# NN22_VCCS_SrcAdapter02_s00.net
KiCad netlist of a schematic drawn in EAGLE
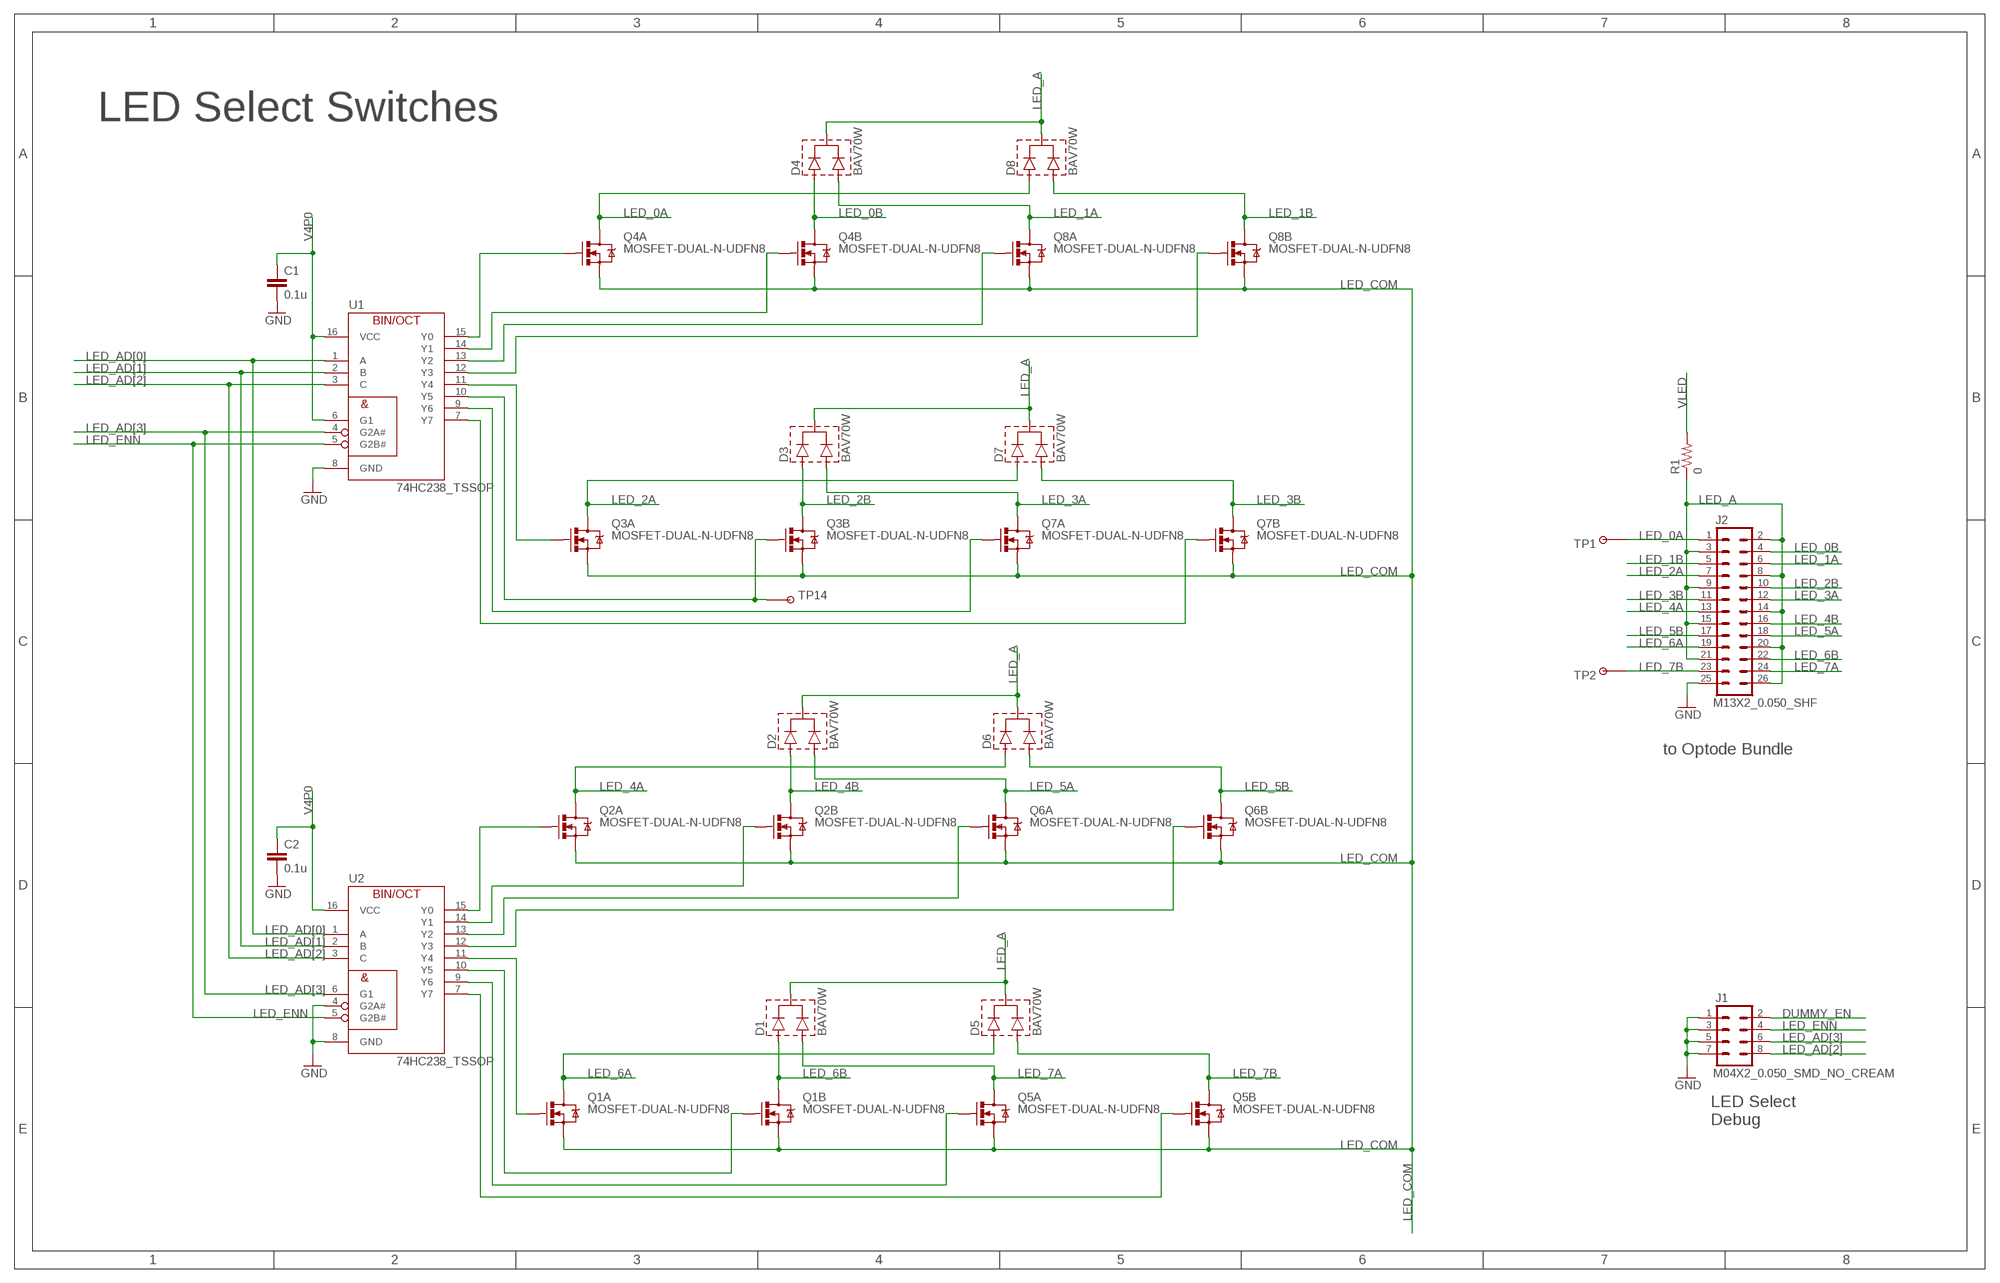
[diagram p0: schematic, sheet 1]
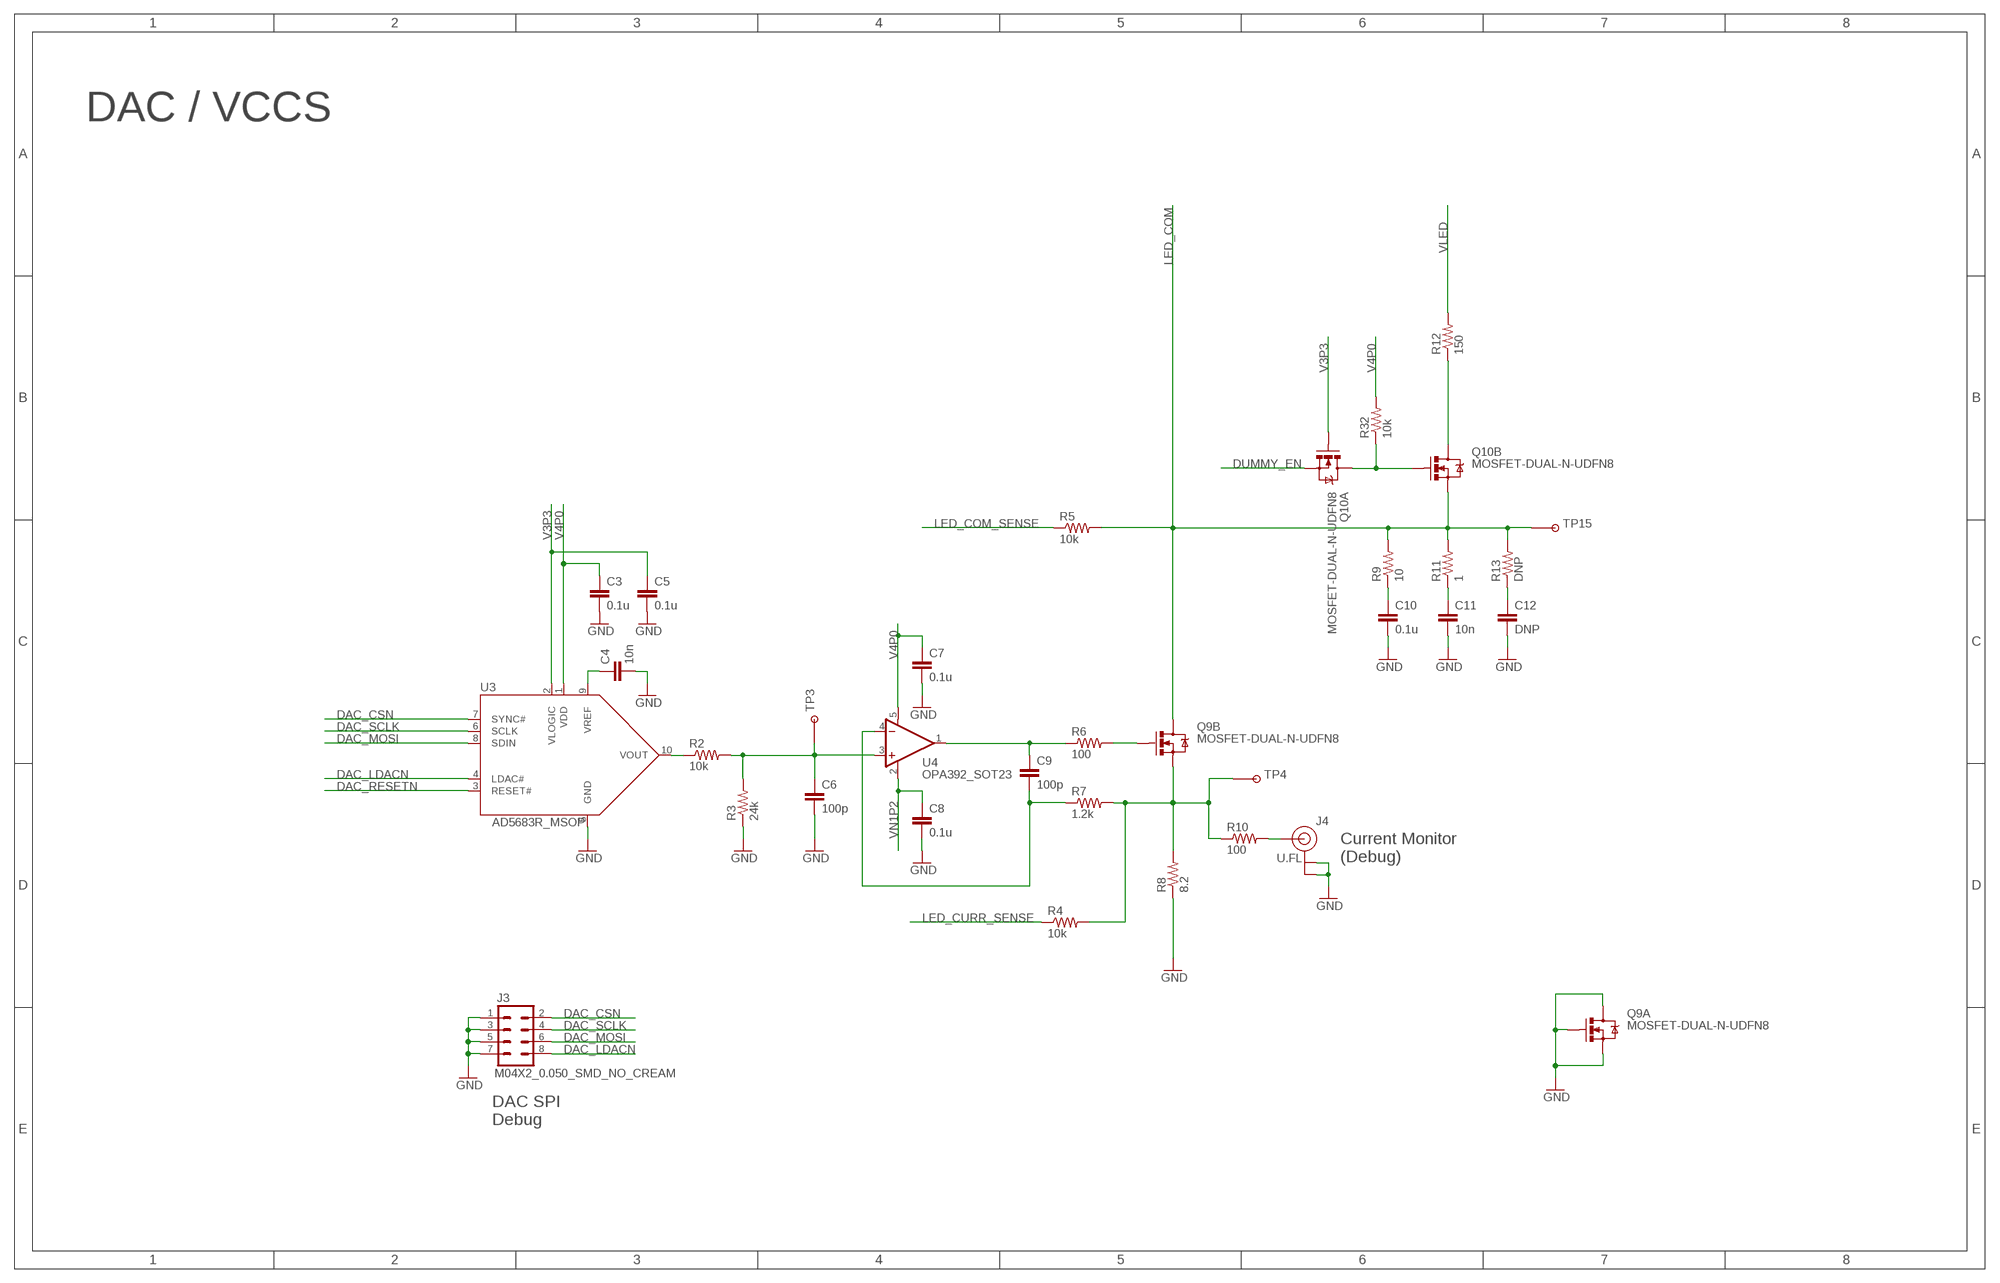
[diagram p1: schematic, sheet 2]
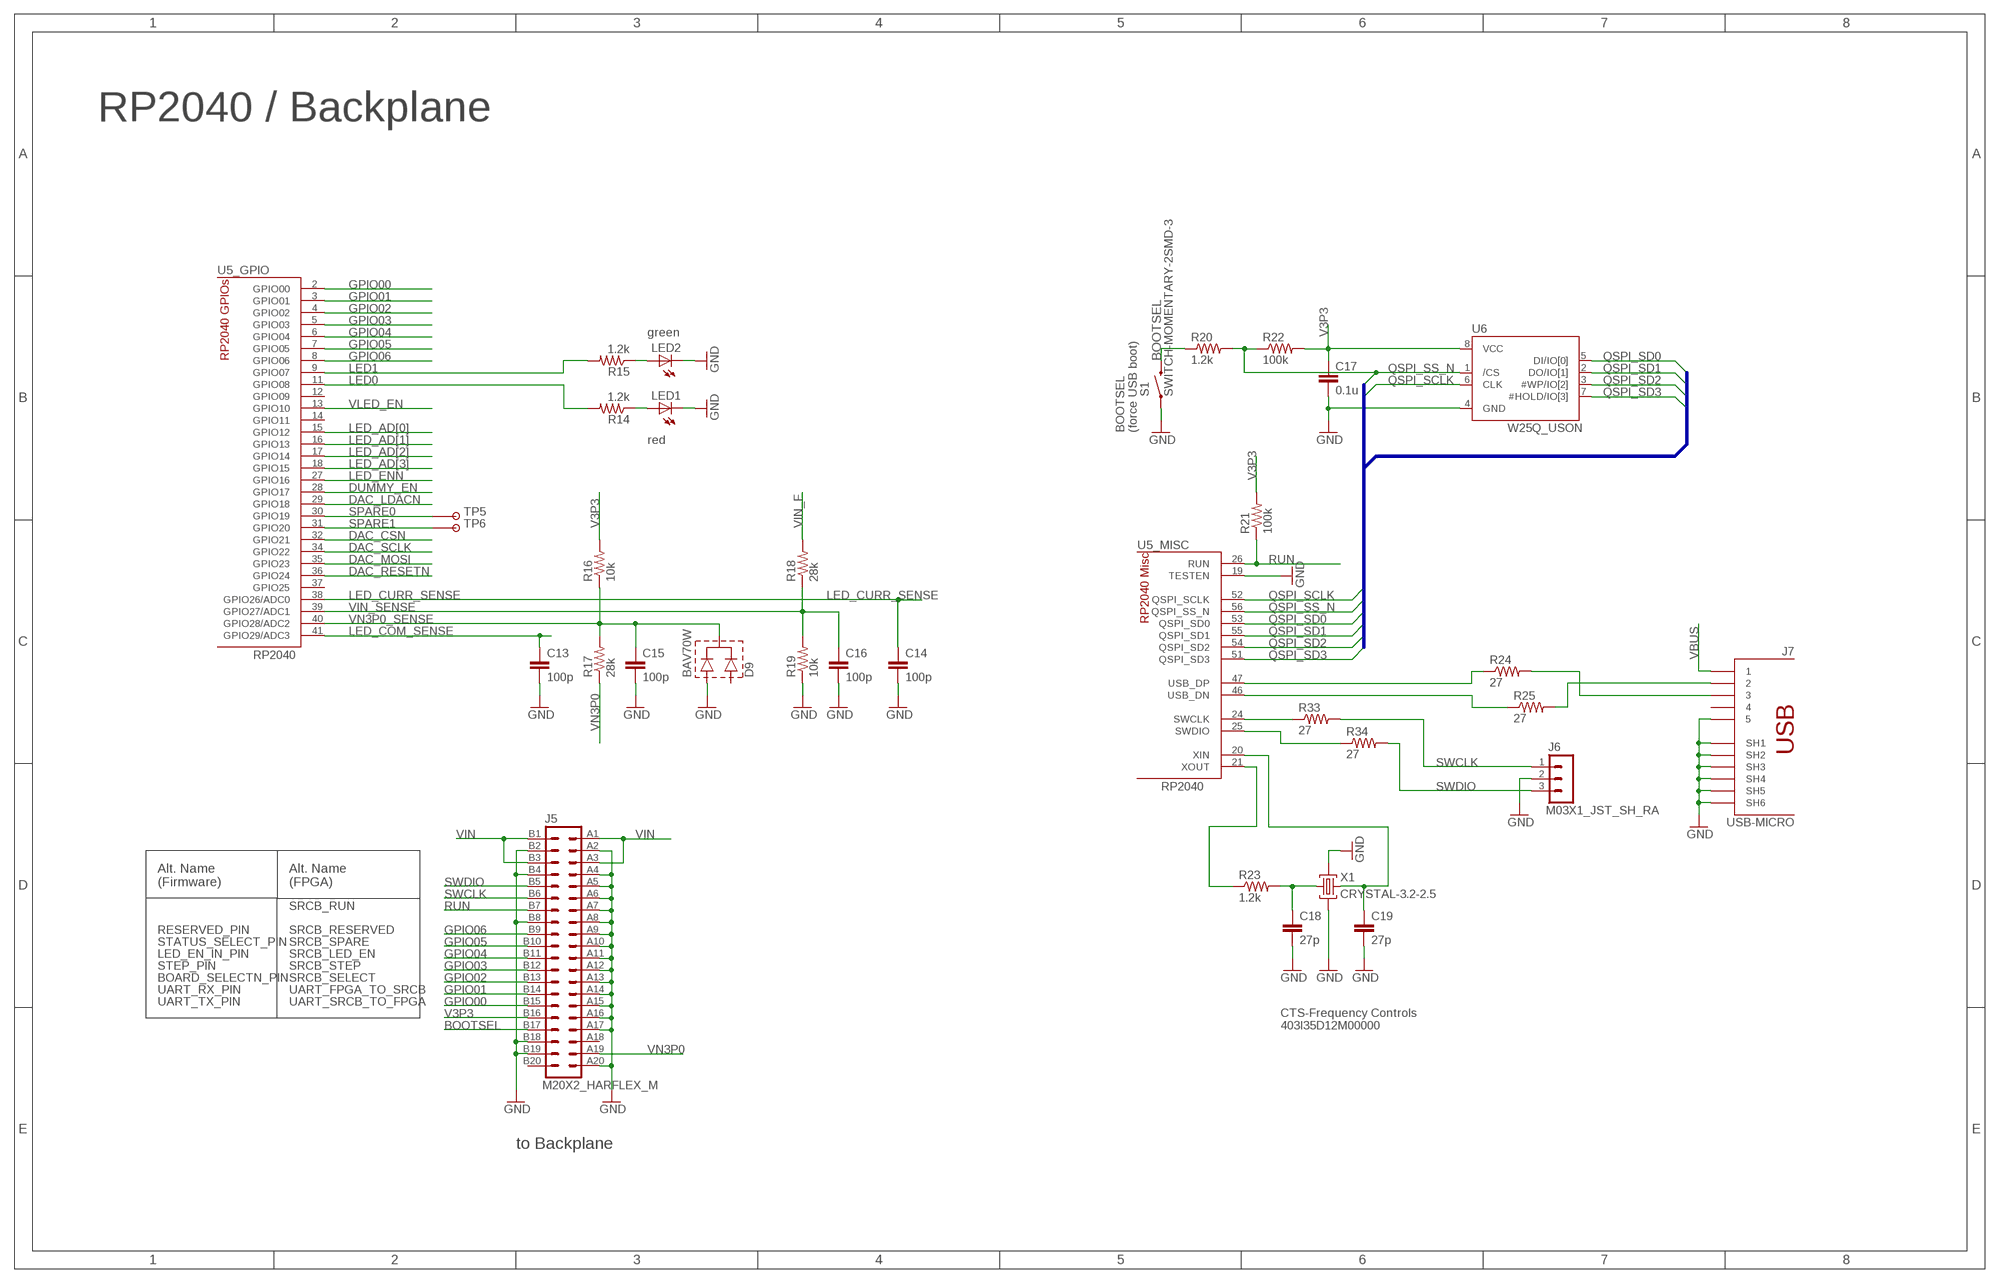
[diagram p2: schematic, sheet 3]
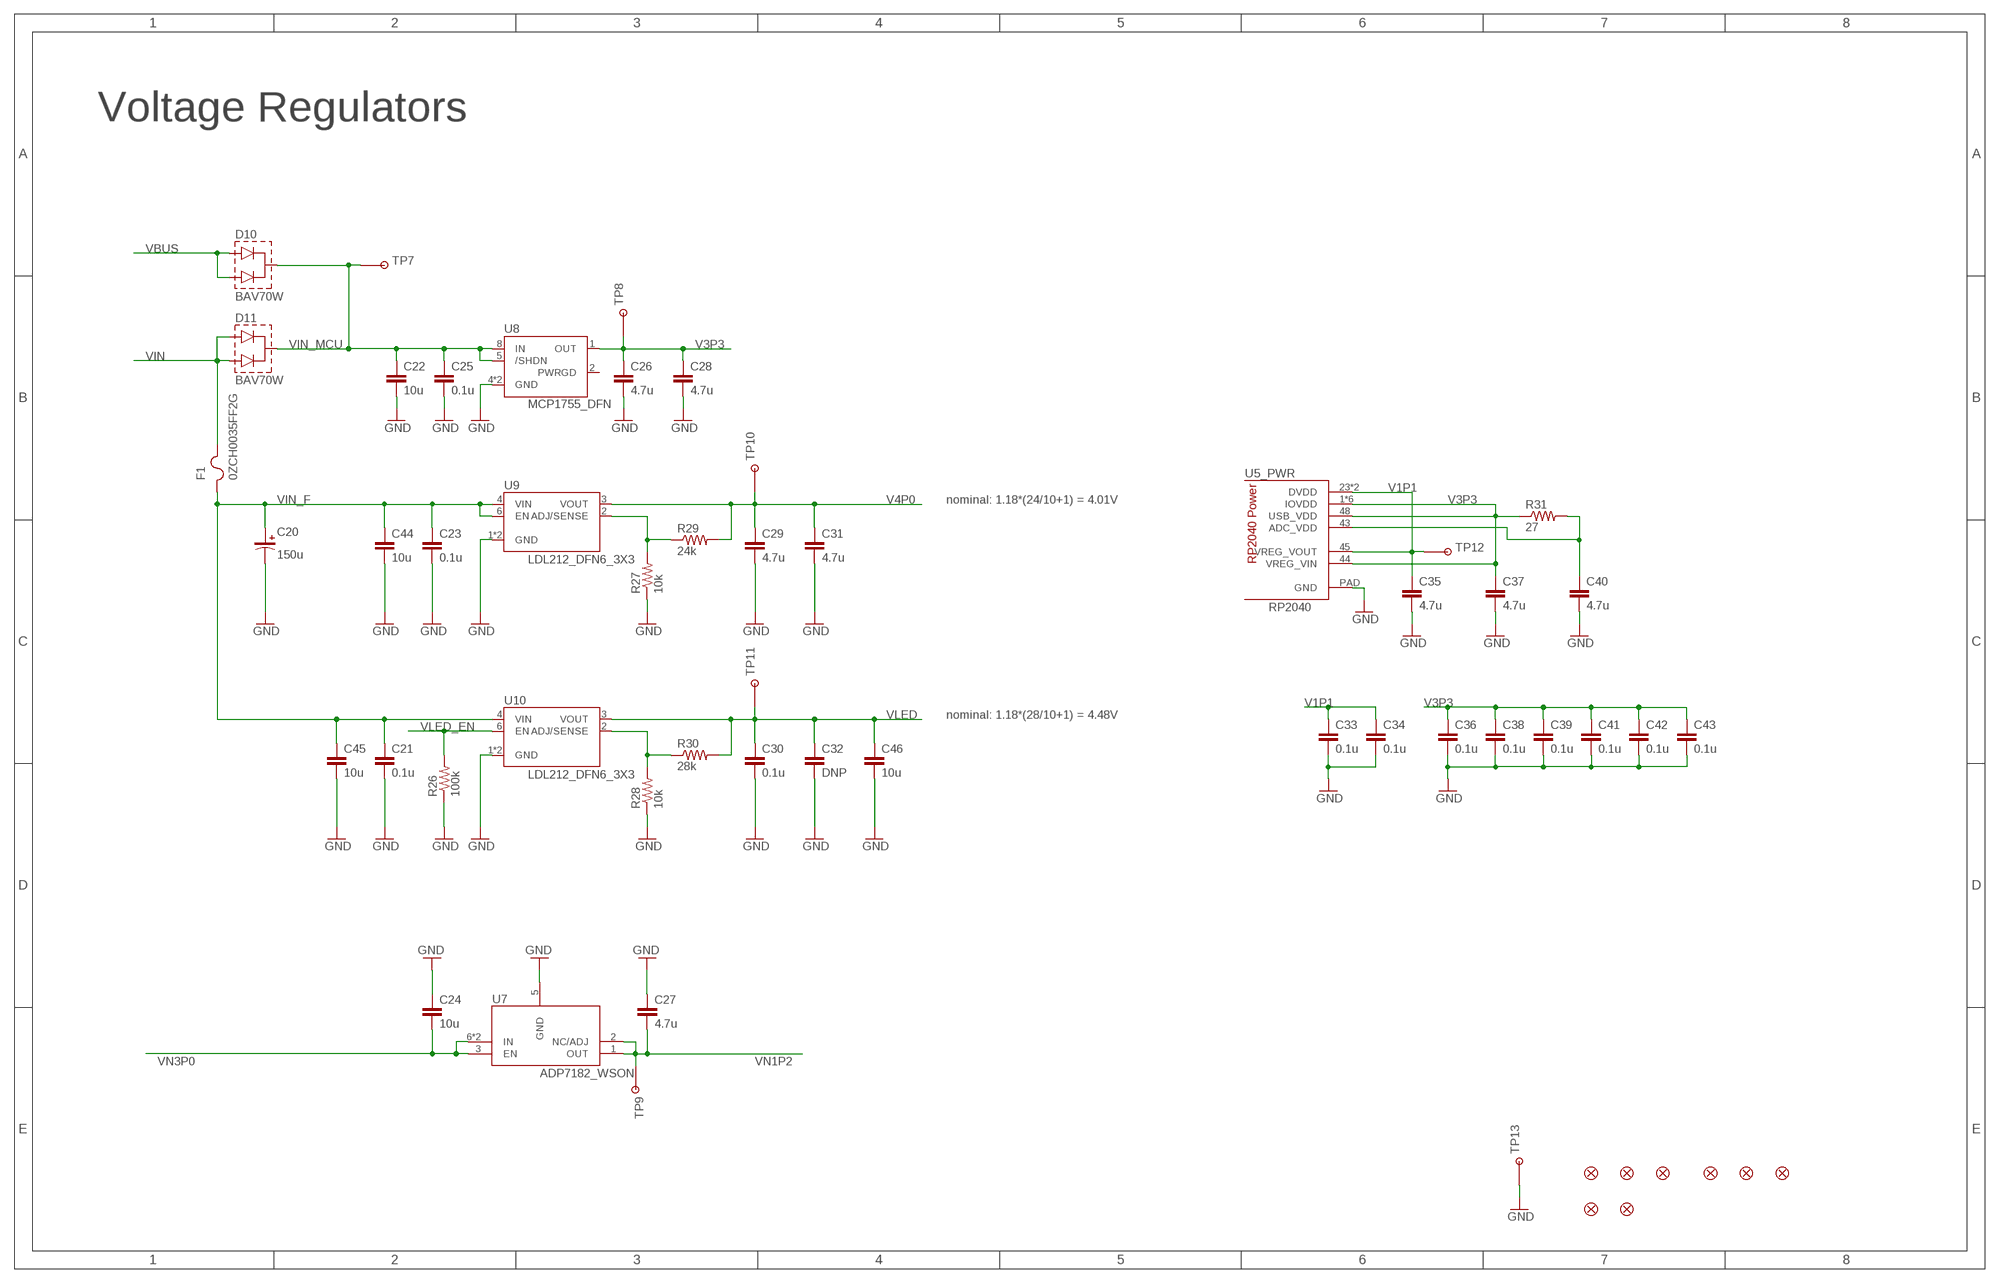
[diagram p3: schematic, sheet 4]

(export (version "E")
  (design (tool "Eeschema 10.0.6"))
  (components
    (comp (ref "C20")
      (value "150u")
      (footprint "eagle-import:2917-CAP")
      (libsource (lib "eagle-import") (part "CAP-POL2917"))
    )
    (comp (ref "C21")
      (value "0.1u")
      (footprint "eagle-import:0402-CAP")
      (libsource (lib "eagle-import") (part "CAP0402-CAP"))
    )
    (comp (ref "C22")
      (value "10u")
      (footprint "eagle-import:0603-CAP")
      (libsource (lib "eagle-import") (part "CAP0603-CAP"))
    )
    (comp (ref "C23")
      (value "0.1u")
      (footprint "eagle-import:0402-CAP")
      (libsource (lib "eagle-import") (part "CAP0402-CAP"))
    )
    (comp (ref "C24")
      (value "10u")
      (footprint "eagle-import:0603-CAP")
      (libsource (lib "eagle-import") (part "CAP0603-CAP"))
    )
    (comp (ref "C25")
      (value "0.1u")
      (footprint "eagle-import:0402-CAP")
      (libsource (lib "eagle-import") (part "CAP0402-CAP"))
    )
    (comp (ref "C26")
      (value "4.7u")
      (footprint "eagle-import:0402-CAP")
      (libsource (lib "eagle-import") (part "CAP0402-CAP"))
    )
    (comp (ref "C27")
      (value "4.7u")
      (footprint "eagle-import:0402-CAP")
      (libsource (lib "eagle-import") (part "CAP0402-CAP"))
    )
    (comp (ref "C28")
      (value "4.7u")
      (footprint "eagle-import:0402-CAP")
      (libsource (lib "eagle-import") (part "CAP0402-CAP"))
    )
    (comp (ref "C29")
      (value "4.7u")
      (footprint "eagle-import:0402-CAP")
      (libsource (lib "eagle-import") (part "CAP0402-CAP"))
    )
    (comp (ref "C30")
      (value "0.1u")
      (footprint "eagle-import:0402-CAP")
      (libsource (lib "eagle-import") (part "CAP0402-CAP"))
    )
    (comp (ref "C31")
      (value "4.7u")
      (footprint "eagle-import:0402-CAP")
      (libsource (lib "eagle-import") (part "CAP0402-CAP"))
    )
    (comp (ref "C32")
      (value "DNP")
      (footprint "eagle-import:0402-CAP")
      (libsource (lib "eagle-import") (part "CAP0402-CAP"))
    )
    (comp (ref "C33")
      (value "0.1u")
      (footprint "eagle-import:0402-CAP")
      (libsource (lib "eagle-import") (part "CAP0402-CAP"))
    )
    (comp (ref "C34")
      (value "0.1u")
      (footprint "eagle-import:0402-CAP")
      (libsource (lib "eagle-import") (part "CAP0402-CAP"))
    )
    (comp (ref "C35")
      (value "4.7u")
      (footprint "eagle-import:0402-CAP")
      (libsource (lib "eagle-import") (part "CAP0402-CAP"))
    )
    (comp (ref "C36")
      (value "0.1u")
      (footprint "eagle-import:0402-CAP")
      (libsource (lib "eagle-import") (part "CAP0402-CAP"))
    )
    (comp (ref "C37")
      (value "4.7u")
      (footprint "eagle-import:0402-CAP")
      (libsource (lib "eagle-import") (part "CAP0402-CAP"))
    )
    (comp (ref "C38")
      (value "0.1u")
      (footprint "eagle-import:0402-CAP")
      (libsource (lib "eagle-import") (part "CAP0402-CAP"))
    )
    (comp (ref "C39")
      (value "0.1u")
      (footprint "eagle-import:0402-CAP")
      (libsource (lib "eagle-import") (part "CAP0402-CAP"))
    )
    (comp (ref "C40")
      (value "4.7u")
      (footprint "eagle-import:0402-CAP")
      (libsource (lib "eagle-import") (part "CAP0402-CAP"))
    )
    (comp (ref "C41")
      (value "0.1u")
      (footprint "eagle-import:0402-CAP")
      (libsource (lib "eagle-import") (part "CAP0402-CAP"))
    )
    (comp (ref "C42")
      (value "0.1u")
      (footprint "eagle-import:0402-CAP")
      (libsource (lib "eagle-import") (part "CAP0402-CAP"))
    )
    (comp (ref "C43")
      (value "0.1u")
      (footprint "eagle-import:0402-CAP")
      (libsource (lib "eagle-import") (part "CAP0402-CAP"))
    )
    (comp (ref "C44")
      (value "10u")
      (footprint "eagle-import:0603-CAP")
      (libsource (lib "eagle-import") (part "CAP0603-CAP"))
    )
    (comp (ref "C45")
      (value "10u")
      (footprint "eagle-import:0603-CAP")
      (libsource (lib "eagle-import") (part "CAP0603-CAP"))
    )
    (comp (ref "C46")
      (value "10u")
      (footprint "eagle-import:0603-CAP")
      (libsource (lib "eagle-import") (part "CAP0603-CAP"))
    )
    (comp (ref "D10")
      (value "BAV70W")
      (footprint "eagle-import:SOT323")
      (libsource (lib "eagle-import") (part "DIODE-COMMON_CATHODE_SOT323"))
    )
    (comp (ref "D11")
      (value "BAV70W")
      (footprint "eagle-import:SOT323")
      (libsource (lib "eagle-import") (part "DIODE-COMMON_CATHODE_SOT323"))
    )
    (comp (ref "F1")
      (value "0ZCH0035FF2G")
      (footprint "eagle-import:1210-FUSE")
      (libsource (lib "eagle-import") (part "FUSE_1210"))
    )
    (comp (ref "FID1")
      (value "FIDUCIALUFIDUCIAL")
      (footprint "eagle-import:MICRO-FIDUCIAL")
      (libsource (lib "eagle-import") (part "FIDUCIALUFIDUCIAL"))
    )
    (comp (ref "FID2")
      (value "FIDUCIALUFIDUCIAL")
      (footprint "eagle-import:MICRO-FIDUCIAL")
      (libsource (lib "eagle-import") (part "FIDUCIALUFIDUCIAL"))
    )
    (comp (ref "FID3")
      (value "FIDUCIALUFIDUCIAL")
      (footprint "eagle-import:MICRO-FIDUCIAL")
      (libsource (lib "eagle-import") (part "FIDUCIALUFIDUCIAL"))
    )
    (comp (ref "FID4")
      (value "FIDUCIALUFIDUCIAL")
      (footprint "eagle-import:MICRO-FIDUCIAL")
      (libsource (lib "eagle-import") (part "FIDUCIALUFIDUCIAL"))
    )
    (comp (ref "FID5")
      (value "FIDUCIALUFIDUCIAL")
      (footprint "eagle-import:MICRO-FIDUCIAL")
      (libsource (lib "eagle-import") (part "FIDUCIALUFIDUCIAL"))
    )
    (comp (ref "FID6")
      (value "FIDUCIALUFIDUCIAL")
      (footprint "eagle-import:MICRO-FIDUCIAL")
      (libsource (lib "eagle-import") (part "FIDUCIALUFIDUCIAL"))
    )
    (comp (ref "FID7")
      (value "FIDUCIALUFIDUCIAL")
      (footprint "eagle-import:MICRO-FIDUCIAL")
      (libsource (lib "eagle-import") (part "FIDUCIALUFIDUCIAL"))
    )
    (comp (ref "FID8")
      (value "FIDUCIALUFIDUCIAL")
      (footprint "eagle-import:MICRO-FIDUCIAL")
      (libsource (lib "eagle-import") (part "FIDUCIALUFIDUCIAL"))
    )
    (comp (ref "R26")
      (value "100k")
      (footprint "eagle-import:0402-RES")
      (libsource (lib "eagle-import") (part "RESISTOR0402-RES"))
    )
    (comp (ref "R27")
      (value "10k")
      (footprint "eagle-import:0402-RES")
      (libsource (lib "eagle-import") (part "RESISTOR0402-RES"))
    )
    (comp (ref "R28")
      (value "10k")
      (footprint "eagle-import:0402-RES")
      (libsource (lib "eagle-import") (part "RESISTOR0402-RES"))
    )
    (comp (ref "R29")
      (value "24k")
      (footprint "eagle-import:0402-RES")
      (libsource (lib "eagle-import") (part "RESISTOR0402-RES"))
    )
    (comp (ref "R30")
      (value "28k")
      (footprint "eagle-import:0402-RES")
      (libsource (lib "eagle-import") (part "RESISTOR0402-RES"))
    )
    (comp (ref "R31")
      (value "27")
      (footprint "eagle-import:0402-RES")
      (libsource (lib "eagle-import") (part "RESISTOR0402-RES"))
    )
    (comp (ref "TP7")
      (value "TESTPOINT_ROUND")
      (footprint "eagle-import:TESTPAD_ROUND")
      (libsource (lib "eagle-import") (part "TESTPOINT_ROUND"))
    )
    (comp (ref "TP8")
      (value "TESTPOINT_ROUND")
      (footprint "eagle-import:TESTPAD_ROUND")
      (libsource (lib "eagle-import") (part "TESTPOINT_ROUND"))
    )
    (comp (ref "TP9")
      (value "TESTPOINT_ROUND")
      (footprint "eagle-import:TESTPAD_ROUND")
      (libsource (lib "eagle-import") (part "TESTPOINT_ROUND"))
    )
    (comp (ref "TP10")
      (value "TESTPOINT_ROUND")
      (footprint "eagle-import:TESTPAD_ROUND")
      (libsource (lib "eagle-import") (part "TESTPOINT_ROUND"))
    )
    (comp (ref "TP11")
      (value "TESTPOINT_ROUND")
      (footprint "eagle-import:TESTPAD_ROUND")
      (libsource (lib "eagle-import") (part "TESTPOINT_ROUND"))
    )
    (comp (ref "TP12")
      (value "TESTPOINTPADSMALL")
      (footprint "eagle-import:TESTPAD_SMALL")
      (libsource (lib "eagle-import") (part "TESTPOINTPADSMALL"))
    )
    (comp (ref "TP13")
      (value "TESTPOINT1X01")
      (footprint "eagle-import:1X01")
      (libsource (lib "eagle-import") (part "TESTPOINT1X01"))
    )
    (comp (ref "U5")
      (value "RP2040")
      (footprint "eagle-import:QFN-56_EP")
      (libsource (lib "eagle-import") (part "RP2040"))
    )
    (comp (ref "U7")
      (value "ADP7182_WSON")
      (footprint "eagle-import:WSON6")
      (libsource (lib "eagle-import") (part "ADP7182_WSON"))
    )
    (comp (ref "U8")
      (value "MCP1755_DFN")
      (footprint "eagle-import:DFN8_2X3MM")
      (libsource (lib "eagle-import") (part "MCP1755_DFN"))
    )
    (comp (ref "U9")
      (value "LDL212_DFN6_3X3")
      (footprint "eagle-import:DFN6_3X3MM")
      (libsource (lib "eagle-import") (part "LDL212_DFN6_3X3"))
    )
    (comp (ref "U10")
      (value "LDL212_DFN6_3X3")
      (footprint "eagle-import:DFN6_3X3MM")
      (libsource (lib "eagle-import") (part "LDL212_DFN6_3X3"))
    )
    (comp (ref "C13")
      (value "100p")
      (footprint "eagle-import:0402-CAP")
      (libsource (lib "eagle-import") (part "CAP0402-CAP"))
    )
    (comp (ref "C14")
      (value "100p")
      (footprint "eagle-import:0402-CAP")
      (libsource (lib "eagle-import") (part "CAP0402-CAP"))
    )
    (comp (ref "C15")
      (value "100p")
      (footprint "eagle-import:0402-CAP")
      (libsource (lib "eagle-import") (part "CAP0402-CAP"))
    )
    (comp (ref "C16")
      (value "100p")
      (footprint "eagle-import:0402-CAP")
      (libsource (lib "eagle-import") (part "CAP0402-CAP"))
    )
    (comp (ref "C17")
      (value "0.1u")
      (footprint "eagle-import:0402-CAP")
      (libsource (lib "eagle-import") (part "CAP0402-CAP"))
    )
    (comp (ref "C18")
      (value "27p")
      (footprint "eagle-import:0402-CAP")
      (libsource (lib "eagle-import") (part "CAP0402-CAP"))
    )
    (comp (ref "C19")
      (value "27p")
      (footprint "eagle-import:0402-CAP")
      (libsource (lib "eagle-import") (part "CAP0402-CAP"))
    )
    (comp (ref "D9")
      (value "BAV70W")
      (footprint "eagle-import:SOT323")
      (libsource (lib "eagle-import") (part "DIODE-COMMON_CATHODE_SOT323"))
    )
    (comp (ref "J5")
      (value "M20X2_HARFLEX_M")
      (footprint "eagle-import:M20X2_HARFLEX_M")
      (libsource (lib "eagle-import") (part "M20X2_HARFLEX_M"))
    )
    (comp (ref "J6")
      (value "M03X1_JST_SH_RA")
      (footprint "eagle-import:M03X1_JST_SH_SM_RA")
      (libsource (lib "eagle-import") (part "M03X1_JST_SH_RA"))
    )
    (comp (ref "J7")
      (value "USB-MICRO")
      (footprint "eagle-import:USB-MICRO")
      (libsource (lib "eagle-import") (part "USB-MICRO"))
    )
    (comp (ref "LED1")
      (value "LED0603")
      (footprint "eagle-import:LED-0603")
      (libsource (lib "eagle-import") (part "LED0603"))
    )
    (comp (ref "LED2")
      (value "LED0603")
      (footprint "eagle-import:LED-0603")
      (libsource (lib "eagle-import") (part "LED0603"))
    )
    (comp (ref "R14")
      (value "1.2k")
      (footprint "eagle-import:0402-RES")
      (libsource (lib "eagle-import") (part "RESISTOR0402-RES"))
    )
    (comp (ref "R15")
      (value "1.2k")
      (footprint "eagle-import:0402-RES")
      (libsource (lib "eagle-import") (part "RESISTOR0402-RES"))
    )
    (comp (ref "R16")
      (value "10k")
      (footprint "eagle-import:0402-RES")
      (libsource (lib "eagle-import") (part "RESISTOR0402-RES"))
    )
    (comp (ref "R17")
      (value "28k")
      (footprint "eagle-import:0402-RES")
      (libsource (lib "eagle-import") (part "RESISTOR0402-RES"))
    )
    (comp (ref "R18")
      (value "28k")
      (footprint "eagle-import:0402-RES")
      (libsource (lib "eagle-import") (part "RESISTOR0402-RES"))
    )
    (comp (ref "R19")
      (value "10k")
      (footprint "eagle-import:0402-RES")
      (libsource (lib "eagle-import") (part "RESISTOR0402-RES"))
    )
    (comp (ref "R20")
      (value "1.2k")
      (footprint "eagle-import:0402-RES")
      (libsource (lib "eagle-import") (part "RESISTOR0402-RES"))
    )
    (comp (ref "R21")
      (value "100k")
      (footprint "eagle-import:0402-RES")
      (libsource (lib "eagle-import") (part "RESISTOR0402-RES"))
    )
    (comp (ref "R22")
      (value "100k")
      (footprint "eagle-import:0402-RES")
      (libsource (lib "eagle-import") (part "RESISTOR0402-RES"))
    )
    (comp (ref "R23")
      (value "1.2k")
      (footprint "eagle-import:0402-RES")
      (libsource (lib "eagle-import") (part "RESISTOR0402-RES"))
    )
    (comp (ref "R24")
      (value "27")
      (footprint "eagle-import:0402-RES")
      (libsource (lib "eagle-import") (part "RESISTOR0402-RES"))
    )
    (comp (ref "R25")
      (value "27")
      (footprint "eagle-import:0402-RES")
      (libsource (lib "eagle-import") (part "RESISTOR0402-RES"))
    )
    (comp (ref "R33")
      (value "27")
      (footprint "eagle-import:0402-RES")
      (libsource (lib "eagle-import") (part "RESISTOR0402-RES"))
    )
    (comp (ref "R34")
      (value "27")
      (footprint "eagle-import:0402-RES")
      (libsource (lib "eagle-import") (part "RESISTOR0402-RES"))
    )
    (comp (ref "S1")
      (value "SWITCH-MOMENTARY-2SMD-3")
      (footprint "eagle-import:TACTILE_SWITCH_SMD-3")
      (libsource (lib "eagle-import") (part "SWITCH-MOMENTARY-2SMD-3"))
    )
    (comp (ref "TP5")
      (value "TESTPOINTPADSMALL")
      (footprint "eagle-import:TESTPAD_SMALL")
      (libsource (lib "eagle-import") (part "TESTPOINTPADSMALL"))
    )
    (comp (ref "TP6")
      (value "TESTPOINTPADSMALL")
      (footprint "eagle-import:TESTPAD_SMALL")
      (libsource (lib "eagle-import") (part "TESTPOINTPADSMALL"))
    )
    (comp (ref "U6")
      (value "W25Q_USON")
      (footprint "eagle-import:USON8L-2X3MM")
      (libsource (lib "eagle-import") (part "W25Q_USON"))
    )
    (comp (ref "X1")
      (value "CRYSTAL-3.2-2.5")
      (footprint "eagle-import:CRYSTAL-3.2-2.5")
      (libsource (lib "eagle-import") (part "CRYSTAL-3.2-2.5"))
    )
    (comp (ref "C3")
      (value "0.1u")
      (footprint "eagle-import:0402-CAP")
      (libsource (lib "eagle-import") (part "CAP0402-CAP"))
    )
    (comp (ref "C4")
      (value "10n")
      (footprint "eagle-import:0402-CAP")
      (libsource (lib "eagle-import") (part "CAP0402-CAP"))
    )
    (comp (ref "C5")
      (value "0.1u")
      (footprint "eagle-import:0402-CAP")
      (libsource (lib "eagle-import") (part "CAP0402-CAP"))
    )
    (comp (ref "C6")
      (value "100p")
      (footprint "eagle-import:0402-CAP")
      (libsource (lib "eagle-import") (part "CAP0402-CAP"))
    )
    (comp (ref "C7")
      (value "0.1u")
      (footprint "eagle-import:0402-CAP")
      (libsource (lib "eagle-import") (part "CAP0402-CAP"))
    )
    (comp (ref "C8")
      (value "0.1u")
      (footprint "eagle-import:0402-CAP")
      (libsource (lib "eagle-import") (part "CAP0402-CAP"))
    )
    (comp (ref "C9")
      (value "100p")
      (footprint "eagle-import:0402-CAP")
      (libsource (lib "eagle-import") (part "CAP0402-CAP"))
    )
    (comp (ref "C10")
      (value "0.1u")
      (footprint "eagle-import:0402-CAP")
      (libsource (lib "eagle-import") (part "CAP0402-CAP"))
    )
    (comp (ref "C11")
      (value "10n")
      (footprint "eagle-import:0402-CAP")
      (libsource (lib "eagle-import") (part "CAP0402-CAP"))
    )
    (comp (ref "C12")
      (value "DNP")
      (footprint "eagle-import:0603-CAP")
      (libsource (lib "eagle-import") (part "CAP0603-CAP"))
    )
    (comp (ref "J3")
      (value "M04X2_0.050_SMD_NO_CREAM")
      (footprint "eagle-import:M04X2_0.050_SMD_NO_CREAM")
      (libsource (lib "eagle-import") (part "M04X2_0.050_SMD_NO_CREAM"))
    )
    (comp (ref "J4")
      (value "U.FL")
      (footprint "eagle-import:U.FL")
      (libsource (lib "eagle-import") (part "U.FL"))
    )
    (comp (ref "Q9")
      (value "MOSFET-DUAL-N-UDFN8")
      (footprint "eagle-import:UDFN8")
      (libsource (lib "eagle-import") (part "MOSFET-DUAL-N-UDFN8"))
    )
    (comp (ref "Q10")
      (value "MOSFET-DUAL-N-UDFN8")
      (footprint "eagle-import:UDFN8")
      (libsource (lib "eagle-import") (part "MOSFET-DUAL-N-UDFN8"))
    )
    (comp (ref "R2")
      (value "10k")
      (footprint "eagle-import:0402-RES")
      (libsource (lib "eagle-import") (part "RESISTOR0402-RES"))
    )
    (comp (ref "R3")
      (value "24k")
      (footprint "eagle-import:0402-RES")
      (libsource (lib "eagle-import") (part "RESISTOR0402-RES"))
    )
    (comp (ref "R4")
      (value "10k")
      (footprint "eagle-import:0402-RES")
      (libsource (lib "eagle-import") (part "RESISTOR0402-RES"))
    )
    (comp (ref "R5")
      (value "10k")
      (footprint "eagle-import:0402-RES")
      (libsource (lib "eagle-import") (part "RESISTOR0402-RES"))
    )
    (comp (ref "R6")
      (value "100")
      (footprint "eagle-import:0402-RES")
      (libsource (lib "eagle-import") (part "RESISTOR0402-RES"))
    )
    (comp (ref "R7")
      (value "1.2k")
      (footprint "eagle-import:0402-RES")
      (libsource (lib "eagle-import") (part "RESISTOR0402-RES"))
    )
    (comp (ref "R8")
      (value "8.2")
      (footprint "eagle-import:R2512")
      (libsource (lib "eagle-import") (part "RESISTOR2512"))
    )
    (comp (ref "R9")
      (value "10")
      (footprint "eagle-import:0603-RES")
      (libsource (lib "eagle-import") (part "RESISTOR0603-RES"))
    )
    (comp (ref "R10")
      (value "100")
      (footprint "eagle-import:0402-RES")
      (libsource (lib "eagle-import") (part "RESISTOR0402-RES"))
    )
    (comp (ref "R11")
      (value "1")
      (footprint "eagle-import:0603-RES")
      (libsource (lib "eagle-import") (part "RESISTOR0603-RES"))
    )
    (comp (ref "R12")
      (value "150")
      (footprint "eagle-import:0603-RES")
      (libsource (lib "eagle-import") (part "RESISTOR0603-RES"))
    )
    (comp (ref "R13")
      (value "DNP")
      (footprint "eagle-import:0603-RES")
      (libsource (lib "eagle-import") (part "RESISTOR0603-RES"))
    )
    (comp (ref "R32")
      (value "10k")
      (footprint "eagle-import:0402-RES")
      (libsource (lib "eagle-import") (part "RESISTOR0402-RES"))
    )
    (comp (ref "TP3")
      (value "TESTPOINT_ROUND")
      (footprint "eagle-import:TESTPAD_ROUND")
      (libsource (lib "eagle-import") (part "TESTPOINT_ROUND"))
    )
    (comp (ref "TP4")
      (value "TESTPOINT_ROUND")
      (footprint "eagle-import:TESTPAD_ROUND")
      (libsource (lib "eagle-import") (part "TESTPOINT_ROUND"))
    )
    (comp (ref "TP15")
      (value "TESTPOINT_ROUND")
      (footprint "eagle-import:TESTPAD_ROUND")
      (libsource (lib "eagle-import") (part "TESTPOINT_ROUND"))
    )
    (comp (ref "U3")
      (value "AD5683R_MSOP")
      (footprint "eagle-import:MSOP10")
      (libsource (lib "eagle-import") (part "AD5683R_MSOP"))
    )
    (comp (ref "U4")
      (value "OPA392_SOT23")
      (footprint "eagle-import:SOT23-5")
      (libsource (lib "eagle-import") (part "OPA392_SOT23"))
    )
    (comp (ref "C1")
      (value "0.1u")
      (footprint "eagle-import:0402-CAP")
      (libsource (lib "eagle-import") (part "CAP0402-CAP"))
    )
    (comp (ref "C2")
      (value "0.1u")
      (footprint "eagle-import:0402-CAP")
      (libsource (lib "eagle-import") (part "CAP0402-CAP"))
    )
    (comp (ref "D1")
      (value "BAV70W")
      (footprint "eagle-import:SOT323")
      (libsource (lib "eagle-import") (part "DIODE-COMMON_CATHODE_SOT323"))
    )
    (comp (ref "D2")
      (value "BAV70W")
      (footprint "eagle-import:SOT323")
      (libsource (lib "eagle-import") (part "DIODE-COMMON_CATHODE_SOT323"))
    )
    (comp (ref "D3")
      (value "BAV70W")
      (footprint "eagle-import:SOT323")
      (libsource (lib "eagle-import") (part "DIODE-COMMON_CATHODE_SOT323"))
    )
    (comp (ref "D4")
      (value "BAV70W")
      (footprint "eagle-import:SOT323")
      (libsource (lib "eagle-import") (part "DIODE-COMMON_CATHODE_SOT323"))
    )
    (comp (ref "D5")
      (value "BAV70W")
      (footprint "eagle-import:SOT323")
      (libsource (lib "eagle-import") (part "DIODE-COMMON_CATHODE_SOT323"))
    )
    (comp (ref "D6")
      (value "BAV70W")
      (footprint "eagle-import:SOT323")
      (libsource (lib "eagle-import") (part "DIODE-COMMON_CATHODE_SOT323"))
    )
    (comp (ref "D7")
      (value "BAV70W")
      (footprint "eagle-import:SOT323")
      (libsource (lib "eagle-import") (part "DIODE-COMMON_CATHODE_SOT323"))
    )
    (comp (ref "D8")
      (value "BAV70W")
      (footprint "eagle-import:SOT323")
      (libsource (lib "eagle-import") (part "DIODE-COMMON_CATHODE_SOT323"))
    )
    (comp (ref "J1")
      (value "M04X2_0.050_SMD_NO_CREAM")
      (footprint "eagle-import:M04X2_0.050_SMD_NO_CREAM")
      (libsource (lib "eagle-import") (part "M04X2_0.050_SMD_NO_CREAM"))
    )
    (comp (ref "J2")
      (value "M13X2_0.050_SHF")
      (footprint "eagle-import:M13X2_0.050_SHF")
      (libsource (lib "eagle-import") (part "M13X2_0.050_SHF"))
    )
    (comp (ref "Q1")
      (value "MOSFET-DUAL-N-UDFN8")
      (footprint "eagle-import:UDFN8")
      (libsource (lib "eagle-import") (part "MOSFET-DUAL-N-UDFN8"))
    )
    (comp (ref "Q2")
      (value "MOSFET-DUAL-N-UDFN8")
      (footprint "eagle-import:UDFN8")
      (libsource (lib "eagle-import") (part "MOSFET-DUAL-N-UDFN8"))
    )
    (comp (ref "Q3")
      (value "MOSFET-DUAL-N-UDFN8")
      (footprint "eagle-import:UDFN8")
      (libsource (lib "eagle-import") (part "MOSFET-DUAL-N-UDFN8"))
    )
    (comp (ref "Q4")
      (value "MOSFET-DUAL-N-UDFN8")
      (footprint "eagle-import:UDFN8")
      (libsource (lib "eagle-import") (part "MOSFET-DUAL-N-UDFN8"))
    )
    (comp (ref "Q5")
      (value "MOSFET-DUAL-N-UDFN8")
      (footprint "eagle-import:UDFN8")
      (libsource (lib "eagle-import") (part "MOSFET-DUAL-N-UDFN8"))
    )
    (comp (ref "Q6")
      (value "MOSFET-DUAL-N-UDFN8")
      (footprint "eagle-import:UDFN8")
      (libsource (lib "eagle-import") (part "MOSFET-DUAL-N-UDFN8"))
    )
    (comp (ref "Q7")
      (value "MOSFET-DUAL-N-UDFN8")
      (footprint "eagle-import:UDFN8")
      (libsource (lib "eagle-import") (part "MOSFET-DUAL-N-UDFN8"))
    )
    (comp (ref "Q8")
      (value "MOSFET-DUAL-N-UDFN8")
      (footprint "eagle-import:UDFN8")
      (libsource (lib "eagle-import") (part "MOSFET-DUAL-N-UDFN8"))
    )
    (comp (ref "R1")
      (value "0")
      (footprint "eagle-import:1206")
      (libsource (lib "eagle-import") (part "RESISTOR1206"))
    )
    (comp (ref "TP1")
      (value "TESTPOINT_ROUND")
      (footprint "eagle-import:TESTPAD_ROUND")
      (libsource (lib "eagle-import") (part "TESTPOINT_ROUND"))
    )
    (comp (ref "TP2")
      (value "TESTPOINT_ROUND")
      (footprint "eagle-import:TESTPAD_ROUND")
      (libsource (lib "eagle-import") (part "TESTPOINT_ROUND"))
    )
    (comp (ref "TP14")
      (value "TESTPOINTPADSMALL")
      (footprint "eagle-import:TESTPAD_SMALL")
      (libsource (lib "eagle-import") (part "TESTPOINTPADSMALL"))
    )
    (comp (ref "U1")
      (value "74HC238_TSSOP")
      (footprint "eagle-import:TSSOP16")
      (libsource (lib "eagle-import") (part "74HC238_TSSOP"))
    )
    (comp (ref "U2")
      (value "74HC238_TSSOP")
      (footprint "eagle-import:TSSOP16")
      (libsource (lib "eagle-import") (part "74HC238_TSSOP"))
    )
  )
  (nets
    (net (code "1") (name "BOOTSEL") (class "Default")
      (node (ref "J5") (pin "B17") (pinfunction "33_B17") (pintype "passive"))
      (node (ref "R20") (pin "1") (pinfunction "1_1") (pintype "passive"))
      (node (ref "S1") (pin "4") (pinfunction "2_4") (pintype "passive"))
    )
    (net (code "2") (name "DAC_CSN") (class "Default")
      (node (ref "J3") (pin "2") (pinfunction "2_2") (pintype "passive"))
      (node (ref "U3") (pin "7") (pinfunction "SYNC#_7") (pintype "input"))
      (node (ref "U5") (pin "32") (pinfunction "GPIO21_32") (pintype "bidirectional"))
    )
    (net (code "3") (name "DAC_LDACN") (class "Default")
      (node (ref "J3") (pin "8") (pinfunction "8_8") (pintype "passive"))
      (node (ref "U3") (pin "4") (pinfunction "LDAC#_4") (pintype "input"))
      (node (ref "U5") (pin "29") (pinfunction "GPIO18_29") (pintype "bidirectional"))
    )
    (net (code "4") (name "DAC_MOSI") (class "Default")
      (node (ref "J3") (pin "6") (pinfunction "6_6") (pintype "passive"))
      (node (ref "U3") (pin "8") (pinfunction "SDIN_8") (pintype "input"))
      (node (ref "U5") (pin "35") (pinfunction "GPIO23_35") (pintype "bidirectional"))
    )
    (net (code "5") (name "DAC_RESETN") (class "Default")
      (node (ref "U3") (pin "3") (pinfunction "RESET#_3") (pintype "input"))
      (node (ref "U5") (pin "36") (pinfunction "GPIO24_36") (pintype "bidirectional"))
    )
    (net (code "6") (name "DAC_SCLK") (class "Default")
      (node (ref "J3") (pin "4") (pinfunction "4_4") (pintype "passive"))
      (node (ref "U3") (pin "6") (pinfunction "SCLK_6") (pintype "input"))
      (node (ref "U5") (pin "34") (pinfunction "GPIO22_34") (pintype "bidirectional"))
    )
    (net (code "7") (name "DUMMY_EN") (class "Default")
      (node (ref "J1") (pin "2") (pinfunction "2_2") (pintype "passive"))
      (node (ref "Q10") (pin "1") (pinfunction "S_1") (pintype "passive"))
      (node (ref "U5") (pin "28") (pinfunction "GPIO17_28") (pintype "bidirectional"))
    )
    (net (code "8") (name "GND") (class "Default")
      (node (ref "C1") (pin "2") (pinfunction "2_2") (pintype "passive"))
      (node (ref "C10") (pin "2") (pinfunction "2_2") (pintype "passive"))
      (node (ref "C11") (pin "2") (pinfunction "2_2") (pintype "passive"))
      (node (ref "C12") (pin "2") (pinfunction "2_2") (pintype "passive"))
      (node (ref "C13") (pin "2") (pinfunction "2_2") (pintype "passive"))
      (node (ref "C14") (pin "2") (pinfunction "2_2") (pintype "passive"))
      (node (ref "C15") (pin "2") (pinfunction "2_2") (pintype "passive"))
      (node (ref "C16") (pin "2") (pinfunction "2_2") (pintype "passive"))
      (node (ref "C17") (pin "2") (pinfunction "2_2") (pintype "passive"))
      (node (ref "C18") (pin "2") (pinfunction "2_2") (pintype "passive"))
      (node (ref "C19") (pin "2") (pinfunction "2_2") (pintype "passive"))
      (node (ref "C2") (pin "2") (pinfunction "2_2") (pintype "passive"))
      (node (ref "C20") (pin "N") (pinfunction "N_N") (pintype "passive"))
      (node (ref "C21") (pin "2") (pinfunction "2_2") (pintype "passive"))
      (node (ref "C22") (pin "2") (pinfunction "2_2") (pintype "passive"))
      (node (ref "C23") (pin "2") (pinfunction "2_2") (pintype "passive"))
      (node (ref "C24") (pin "1") (pinfunction "1_1") (pintype "passive"))
      (node (ref "C25") (pin "2") (pinfunction "2_2") (pintype "passive"))
      (node (ref "C26") (pin "2") (pinfunction "2_2") (pintype "passive"))
      (node (ref "C27") (pin "1") (pinfunction "1_1") (pintype "passive"))
      (node (ref "C28") (pin "2") (pinfunction "2_2") (pintype "passive"))
      (node (ref "C29") (pin "2") (pinfunction "2_2") (pintype "passive"))
      (node (ref "C3") (pin "2") (pinfunction "2_2") (pintype "passive"))
      (node (ref "C30") (pin "2") (pinfunction "2_2") (pintype "passive"))
      (node (ref "C31") (pin "2") (pinfunction "2_2") (pintype "passive"))
      (node (ref "C32") (pin "2") (pinfunction "2_2") (pintype "passive"))
      (node (ref "C33") (pin "2") (pinfunction "2_2") (pintype "passive"))
      (node (ref "C34") (pin "2") (pinfunction "2_2") (pintype "passive"))
      (node (ref "C35") (pin "2") (pinfunction "2_2") (pintype "passive"))
      (node (ref "C36") (pin "2") (pinfunction "2_2") (pintype "passive"))
      (node (ref "C37") (pin "2") (pinfunction "2_2") (pintype "passive"))
      (node (ref "C38") (pin "2") (pinfunction "2_2") (pintype "passive"))
      (node (ref "C39") (pin "2") (pinfunction "2_2") (pintype "passive"))
      (node (ref "C4") (pin "2") (pinfunction "2_2") (pintype "passive"))
      (node (ref "C40") (pin "2") (pinfunction "2_2") (pintype "passive"))
      (node (ref "C41") (pin "2") (pinfunction "2_2") (pintype "passive"))
      (node (ref "C42") (pin "2") (pinfunction "2_2") (pintype "passive"))
      (node (ref "C43") (pin "2") (pinfunction "2_2") (pintype "passive"))
      (node (ref "C44") (pin "2") (pinfunction "2_2") (pintype "passive"))
      (node (ref "C45") (pin "2") (pinfunction "2_2") (pintype "passive"))
      (node (ref "C46") (pin "2") (pinfunction "2_2") (pintype "passive"))
      (node (ref "C5") (pin "2") (pinfunction "2_2") (pintype "passive"))
      (node (ref "C6") (pin "2") (pinfunction "2_2") (pintype "passive"))
      (node (ref "C7") (pin "2") (pinfunction "2_2") (pintype "passive"))
      (node (ref "C8") (pin "2") (pinfunction "2_2") (pintype "passive"))
      (node (ref "D9") (pin "2") (pinfunction "A2_2") (pintype "bidirectional"))
      (node (ref "J1") (pin "1") (pinfunction "1_1") (pintype "passive"))
      (node (ref "J1") (pin "3") (pinfunction "3_3") (pintype "passive"))
      (node (ref "J1") (pin "5") (pinfunction "5_5") (pintype "passive"))
      (node (ref "J1") (pin "7") (pinfunction "7_7") (pintype "passive"))
      (node (ref "J2") (pin "25") (pinfunction "25_25") (pintype "passive"))
      (node (ref "J3") (pin "1") (pinfunction "1_1") (pintype "passive"))
      (node (ref "J3") (pin "3") (pinfunction "3_3") (pintype "passive"))
      (node (ref "J3") (pin "5") (pinfunction "5_5") (pintype "passive"))
      (node (ref "J3") (pin "7") (pinfunction "7_7") (pintype "passive"))
      (node (ref "J4") (pin "P$1") (pinfunction "GND_P$1") (pintype "bidirectional"))
      (node (ref "J4") (pin "P$2") (pinfunction "GND_P$2") (pintype "bidirectional"))
      (node (ref "J5") (pin "A10") (pinfunction "20_A10") (pintype "passive"))
      (node (ref "J5") (pin "A11") (pinfunction "22_A11") (pintype "passive"))
      (node (ref "J5") (pin "A12") (pinfunction "24_A12") (pintype "passive"))
      (node (ref "J5") (pin "A13") (pinfunction "26_A13") (pintype "passive"))
      (node (ref "J5") (pin "A14") (pinfunction "28_A14") (pintype "passive"))
      (node (ref "J5") (pin "A15") (pinfunction "30_A15") (pintype "passive"))
      (node (ref "J5") (pin "A16") (pinfunction "32_A16") (pintype "passive"))
      (node (ref "J5") (pin "A17") (pinfunction "34_A17") (pintype "passive"))
      (node (ref "J5") (pin "A2") (pinfunction "4_A2") (pintype "passive"))
      (node (ref "J5") (pin "A20") (pinfunction "40_A20") (pintype "passive"))
      (node (ref "J5") (pin "A4") (pinfunction "8_A4") (pintype "passive"))
      (node (ref "J5") (pin "A5") (pinfunction "10_A5") (pintype "passive"))
      (node (ref "J5") (pin "A6") (pinfunction "12_A6") (pintype "passive"))
      (node (ref "J5") (pin "A7") (pinfunction "14_A7") (pintype "passive"))
      (node (ref "J5") (pin "A8") (pinfunction "16_A8") (pintype "passive"))
      (node (ref "J5") (pin "A9") (pinfunction "18_A9") (pintype "passive"))
      (node (ref "J5") (pin "B18") (pinfunction "35_B18") (pintype "passive"))
      (node (ref "J5") (pin "B19") (pinfunction "37_B19") (pintype "passive"))
      (node (ref "J5") (pin "B2") (pinfunction "3_B2") (pintype "passive"))
      (node (ref "J5") (pin "B4") (pinfunction "7_B4") (pintype "passive"))
      (node (ref "J5") (pin "B8") (pinfunction "15_B8") (pintype "passive"))
      (node (ref "J6") (pin "2") (pinfunction "2_2") (pintype "passive"))
      (node (ref "J7") (pin "5") (pinfunction "5_5") (pintype "bidirectional"))
      (node (ref "J7") (pin "SH1") (pinfunction "SH1_SH1") (pintype "bidirectional"))
      (node (ref "J7") (pin "SH2") (pinfunction "SH2_SH2") (pintype "bidirectional"))
      (node (ref "J7") (pin "SH3") (pinfunction "SH3_SH3") (pintype "bidirectional"))
      (node (ref "J7") (pin "SH4") (pinfunction "SH4_SH4") (pintype "bidirectional"))
      (node (ref "J7") (pin "SH5") (pinfunction "SH5_SH5") (pintype "bidirectional"))
      (node (ref "J7") (pin "SH6") (pinfunction "SH6_SH6") (pintype "bidirectional"))
      (node (ref "LED1") (pin "C") (pinfunction "C_C") (pintype "passive"))
      (node (ref "LED2") (pin "C") (pinfunction "C_C") (pintype "passive"))
      (node (ref "Q9") (pin "1") (pinfunction "S_1") (pintype "passive"))
      (node (ref "Q9") (pin "2") (pinfunction "G_2") (pintype "passive"))
      (node (ref "Q9") (pin "6") (pinfunction "D_6") (pintype "passive"))
      (node (ref "Q9") (pin "P1") (pinfunction "D_P1") (pintype "passive"))
      (node (ref "R19") (pin "1") (pinfunction "1_1") (pintype "passive"))
      (node (ref "R26") (pin "1") (pinfunction "1_1") (pintype "passive"))
      (node (ref "R27") (pin "1") (pinfunction "1_1") (pintype "passive"))
      (node (ref "R28") (pin "1") (pinfunction "1_1") (pintype "passive"))
      (node (ref "R3") (pin "1") (pinfunction "1_1") (pintype "passive"))
      (node (ref "R8") (pin "1") (pinfunction "1_1") (pintype "passive"))
      (node (ref "S1") (pin "1") (pinfunction "1_1") (pintype "passive"))
      (node (ref "TP13") (pin "1") (pinfunction "P$1_1") (pintype "bidirectional"))
      (node (ref "U1") (pin "8") (pinfunction "GND_8") (pintype "power_in"))
      (node (ref "U10") (pin "1") (pinfunction "GND_1") (pintype "power_in"))
      (node (ref "U10") (pin "PAD") (pinfunction "GND_PAD") (pintype "power_in"))
      (node (ref "U2") (pin "4") (pinfunction "G2A#_4") (pintype "input"))
      (node (ref "U2") (pin "8") (pinfunction "GND_8") (pintype "power_in"))
      (node (ref "U3") (pin "5") (pinfunction "GND_5") (pintype "power_in"))
      (node (ref "U5") (pin "19") (pinfunction "TESTEN_19") (pintype "input"))
      (node (ref "U5") (pin "PAD") (pinfunction "GND_PAD") (pintype "power_in"))
      (node (ref "U6") (pin "4") (pinfunction "GND_4") (pintype "power_in"))
      (node (ref "U7") (pin "5") (pinfunction "GND_5") (pintype "bidirectional"))
      (node (ref "U8") (pin "4") (pinfunction "GND_4") (pintype "power_in"))
      (node (ref "U8") (pin "P") (pinfunction "GND_P") (pintype "power_in"))
      (node (ref "U9") (pin "1") (pinfunction "GND_1") (pintype "power_in"))
      (node (ref "U9") (pin "PAD") (pinfunction "GND_PAD") (pintype "power_in"))
      (node (ref "X1") (pin "2") (pinfunction "GND_2") (pintype "passive"))
      (node (ref "X1") (pin "4") (pinfunction "GND_4") (pintype "passive"))
    )
    (net (code "9") (name "GPIO00") (class "Default")
      (node (ref "J5") (pin "B15") (pinfunction "29_B15") (pintype "passive"))
      (node (ref "U5") (pin "2") (pinfunction "GPIO00_2") (pintype "bidirectional"))
    )
    (net (code "10") (name "GPIO01") (class "Default")
      (node (ref "J5") (pin "B14") (pinfunction "27_B14") (pintype "passive"))
      (node (ref "U5") (pin "3") (pinfunction "GPIO01_3") (pintype "bidirectional"))
    )
    (net (code "11") (name "GPIO02") (class "Default")
      (node (ref "J5") (pin "B13") (pinfunction "25_B13") (pintype "passive"))
      (node (ref "U5") (pin "4") (pinfunction "GPIO02_4") (pintype "bidirectional"))
    )
    (net (code "12") (name "GPIO03") (class "Default")
      (node (ref "J5") (pin "B12") (pinfunction "23_B12") (pintype "passive"))
      (node (ref "U5") (pin "5") (pinfunction "GPIO03_5") (pintype "bidirectional"))
    )
    (net (code "13") (name "GPIO04") (class "Default")
      (node (ref "J5") (pin "B11") (pinfunction "21_B11") (pintype "passive"))
      (node (ref "U5") (pin "6") (pinfunction "GPIO04_6") (pintype "bidirectional"))
    )
    (net (code "14") (name "GPIO05") (class "Default")
      (node (ref "J5") (pin "B10") (pinfunction "19_B10") (pintype "passive"))
      (node (ref "U5") (pin "7") (pinfunction "GPIO05_7") (pintype "bidirectional"))
    )
    (net (code "15") (name "GPIO06") (class "Default")
      (node (ref "J5") (pin "B9") (pinfunction "17_B9") (pintype "passive"))
      (node (ref "U5") (pin "8") (pinfunction "GPIO06_8") (pintype "bidirectional"))
    )
    (net (code "16") (name "LED0") (class "Default")
      (node (ref "R14") (pin "2") (pinfunction "2_2") (pintype "passive"))
      (node (ref "U5") (pin "11") (pinfunction "GPIO08_11") (pintype "bidirectional"))
    )
    (net (code "17") (name "LED1") (class "Default")
      (node (ref "R15") (pin "2") (pinfunction "2_2") (pintype "passive"))
      (node (ref "U5") (pin "9") (pinfunction "GPIO07_9") (pintype "bidirectional"))
    )
    (net (code "18") (name "LED_0A") (class "Default")
      (node (ref "D8") (pin "1") (pinfunction "A1_1") (pintype "bidirectional"))
      (node (ref "J2") (pin "1") (pinfunction "1_1") (pintype "passive"))
      (node (ref "Q4") (pin "6") (pinfunction "D_6") (pintype "passive"))
      (node (ref "Q4") (pin "P1") (pinfunction "D_P1") (pintype "passive"))
      (node (ref "TP1") (pin "P$1") (pinfunction "P$1_P$1") (pintype "bidirectional"))
    )
    (net (code "19") (name "LED_0B") (class "Default")
      (node (ref "D4") (pin "1") (pinfunction "A1_1") (pintype "bidirectional"))
      (node (ref "J2") (pin "4") (pinfunction "4_4") (pintype "passive"))
      (node (ref "Q4") (pin "3") (pinfunction "D_3") (pintype "passive"))
      (node (ref "Q4") (pin "P2") (pinfunction "D_P2") (pintype "passive"))
    )
    (net (code "20") (name "LED_1A") (class "Default")
      (node (ref "D4") (pin "2") (pinfunction "A2_2") (pintype "bidirectional"))
      (node (ref "J2") (pin "6") (pinfunction "6_6") (pintype "passive"))
      (node (ref "Q8") (pin "6") (pinfunction "D_6") (pintype "passive"))
      (node (ref "Q8") (pin "P1") (pinfunction "D_P1") (pintype "passive"))
    )
    (net (code "21") (name "LED_1B") (class "Default")
      (node (ref "D8") (pin "2") (pinfunction "A2_2") (pintype "bidirectional"))
      (node (ref "J2") (pin "5") (pinfunction "5_5") (pintype "passive"))
      (node (ref "Q8") (pin "3") (pinfunction "D_3") (pintype "passive"))
      (node (ref "Q8") (pin "P2") (pinfunction "D_P2") (pintype "passive"))
    )
    (net (code "22") (name "LED_2A") (class "Default")
      (node (ref "D7") (pin "1") (pinfunction "A1_1") (pintype "bidirectional"))
      (node (ref "J2") (pin "7") (pinfunction "7_7") (pintype "passive"))
      (node (ref "Q3") (pin "6") (pinfunction "D_6") (pintype "passive"))
      (node (ref "Q3") (pin "P1") (pinfunction "D_P1") (pintype "passive"))
    )
    (net (code "23") (name "LED_2B") (class "Default")
      (node (ref "D3") (pin "1") (pinfunction "A1_1") (pintype "bidirectional"))
      (node (ref "J2") (pin "10") (pinfunction "10_10") (pintype "passive"))
      (node (ref "Q3") (pin "3") (pinfunction "D_3") (pintype "passive"))
      (node (ref "Q3") (pin "P2") (pinfunction "D_P2") (pintype "passive"))
    )
    (net (code "24") (name "LED_3A") (class "Default")
      (node (ref "D3") (pin "2") (pinfunction "A2_2") (pintype "bidirectional"))
      (node (ref "J2") (pin "12") (pinfunction "12_12") (pintype "passive"))
      (node (ref "Q7") (pin "6") (pinfunction "D_6") (pintype "passive"))
      (node (ref "Q7") (pin "P1") (pinfunction "D_P1") (pintype "passive"))
    )
    (net (code "25") (name "LED_3B") (class "Default")
      (node (ref "D7") (pin "2") (pinfunction "A2_2") (pintype "bidirectional"))
      (node (ref "J2") (pin "11") (pinfunction "11_11") (pintype "passive"))
      (node (ref "Q7") (pin "3") (pinfunction "D_3") (pintype "passive"))
      (node (ref "Q7") (pin "P2") (pinfunction "D_P2") (pintype "passive"))
    )
    (net (code "26") (name "LED_4A") (class "Default")
      (node (ref "D6") (pin "1") (pinfunction "A1_1") (pintype "bidirectional"))
      (node (ref "J2") (pin "13") (pinfunction "13_13") (pintype "passive"))
      (node (ref "Q2") (pin "6") (pinfunction "D_6") (pintype "passive"))
      (node (ref "Q2") (pin "P1") (pinfunction "D_P1") (pintype "passive"))
    )
    (net (code "27") (name "LED_4B") (class "Default")
      (node (ref "D2") (pin "1") (pinfunction "A1_1") (pintype "bidirectional"))
      (node (ref "J2") (pin "16") (pinfunction "16_16") (pintype "passive"))
      (node (ref "Q2") (pin "3") (pinfunction "D_3") (pintype "passive"))
      (node (ref "Q2") (pin "P2") (pinfunction "D_P2") (pintype "passive"))
    )
    (net (code "28") (name "LED_5A") (class "Default")
      (node (ref "D2") (pin "2") (pinfunction "A2_2") (pintype "bidirectional"))
      (node (ref "J2") (pin "18") (pinfunction "18_18") (pintype "passive"))
      (node (ref "Q6") (pin "6") (pinfunction "D_6") (pintype "passive"))
      (node (ref "Q6") (pin "P1") (pinfunction "D_P1") (pintype "passive"))
    )
    (net (code "29") (name "LED_5B") (class "Default")
      (node (ref "D6") (pin "2") (pinfunction "A2_2") (pintype "bidirectional"))
      (node (ref "J2") (pin "17") (pinfunction "17_17") (pintype "passive"))
      (node (ref "Q6") (pin "3") (pinfunction "D_3") (pintype "passive"))
      (node (ref "Q6") (pin "P2") (pinfunction "D_P2") (pintype "passive"))
    )
    (net (code "30") (name "LED_6A") (class "Default")
      (node (ref "D5") (pin "1") (pinfunction "A1_1") (pintype "bidirectional"))
      (node (ref "J2") (pin "19") (pinfunction "19_19") (pintype "passive"))
      (node (ref "Q1") (pin "6") (pinfunction "D_6") (pintype "passive"))
      (node (ref "Q1") (pin "P1") (pinfunction "D_P1") (pintype "passive"))
    )
    (net (code "31") (name "LED_6B") (class "Default")
      (node (ref "D1") (pin "1") (pinfunction "A1_1") (pintype "bidirectional"))
      (node (ref "J2") (pin "22") (pinfunction "22_22") (pintype "passive"))
      (node (ref "Q1") (pin "3") (pinfunction "D_3") (pintype "passive"))
      (node (ref "Q1") (pin "P2") (pinfunction "D_P2") (pintype "passive"))
    )
    (net (code "32") (name "LED_7A") (class "Default")
      (node (ref "D1") (pin "2") (pinfunction "A2_2") (pintype "bidirectional"))
      (node (ref "J2") (pin "24") (pinfunction "24_24") (pintype "passive"))
      (node (ref "Q5") (pin "6") (pinfunction "D_6") (pintype "passive"))
      (node (ref "Q5") (pin "P1") (pinfunction "D_P1") (pintype "passive"))
    )
    (net (code "33") (name "LED_7B") (class "Default")
      (node (ref "D5") (pin "2") (pinfunction "A2_2") (pintype "bidirectional"))
      (node (ref "J2") (pin "23") (pinfunction "23_23") (pintype "passive"))
      (node (ref "Q5") (pin "3") (pinfunction "D_3") (pintype "passive"))
      (node (ref "Q5") (pin "P2") (pinfunction "D_P2") (pintype "passive"))
      (node (ref "TP2") (pin "P$1") (pinfunction "P$1_P$1") (pintype "bidirectional"))
    )
    (net (code "34") (name "LED_A") (class "Default")
      (node (ref "D1") (pin "3") (pinfunction "C_3") (pintype "bidirectional"))
      (node (ref "D2") (pin "3") (pinfunction "C_3") (pintype "bidirectional"))
      (node (ref "D3") (pin "3") (pinfunction "C_3") (pintype "bidirectional"))
      (node (ref "D4") (pin "3") (pinfunction "C_3") (pintype "bidirectional"))
      (node (ref "D5") (pin "3") (pinfunction "C_3") (pintype "bidirectional"))
      (node (ref "D6") (pin "3") (pinfunction "C_3") (pintype "bidirectional"))
      (node (ref "D7") (pin "3") (pinfunction "C_3") (pintype "bidirectional"))
      (node (ref "D8") (pin "3") (pinfunction "C_3") (pintype "bidirectional"))
      (node (ref "J2") (pin "14") (pinfunction "14_14") (pintype "passive"))
      (node (ref "J2") (pin "15") (pinfunction "15_15") (pintype "passive"))
      (node (ref "J2") (pin "2") (pinfunction "2_2") (pintype "passive"))
      (node (ref "J2") (pin "20") (pinfunction "20_20") (pintype "passive"))
      (node (ref "J2") (pin "21") (pinfunction "21_21") (pintype "passive"))
      (node (ref "J2") (pin "26") (pinfunction "26_26") (pintype "passive"))
      (node (ref "J2") (pin "3") (pinfunction "3_3") (pintype "passive"))
      (node (ref "J2") (pin "8") (pinfunction "8_8") (pintype "passive"))
      (node (ref "J2") (pin "9") (pinfunction "9_9") (pintype "passive"))
      (node (ref "R1") (pin "1") (pinfunction "1_1") (pintype "passive"))
    )
    (net (code "35") (name "LED_AD[0]") (class "Default")
      (node (ref "U1") (pin "1") (pinfunction "A_1") (pintype "input"))
      (node (ref "U2") (pin "1") (pinfunction "A_1") (pintype "input"))
      (node (ref "U5") (pin "15") (pinfunction "GPIO12_15") (pintype "bidirectional"))
    )
    (net (code "36") (name "LED_AD[1]") (class "Default")
      (node (ref "U1") (pin "2") (pinfunction "B_2") (pintype "input"))
      (node (ref "U2") (pin "2") (pinfunction "B_2") (pintype "input"))
      (node (ref "U5") (pin "16") (pinfunction "GPIO13_16") (pintype "bidirectional"))
    )
    (net (code "37") (name "LED_AD[2]") (class "Default")
      (node (ref "J1") (pin "8") (pinfunction "8_8") (pintype "passive"))
      (node (ref "U1") (pin "3") (pinfunction "C_3") (pintype "input"))
      (node (ref "U2") (pin "3") (pinfunction "C_3") (pintype "input"))
      (node (ref "U5") (pin "17") (pinfunction "GPIO14_17") (pintype "bidirectional"))
    )
    (net (code "38") (name "LED_AD[3]") (class "Default")
      (node (ref "J1") (pin "6") (pinfunction "6_6") (pintype "passive"))
      (node (ref "U1") (pin "4") (pinfunction "G2A#_4") (pintype "input"))
      (node (ref "U2") (pin "6") (pinfunction "G1_6") (pintype "input"))
      (node (ref "U5") (pin "18") (pinfunction "GPIO15_18") (pintype "bidirectional"))
    )
    (net (code "39") (name "LED_COM") (class "Default")
      (node (ref "Q1") (pin "1") (pinfunction "S_1") (pintype "passive"))
      (node (ref "Q1") (pin "4") (pinfunction "S_4") (pintype "passive"))
      (node (ref "Q10") (pin "4") (pinfunction "S_4") (pintype "passive"))
      (node (ref "Q2") (pin "1") (pinfunction "S_1") (pintype "passive"))
      (node (ref "Q2") (pin "4") (pinfunction "S_4") (pintype "passive"))
      (node (ref "Q3") (pin "1") (pinfunction "S_1") (pintype "passive"))
      (node (ref "Q3") (pin "4") (pinfunction "S_4") (pintype "passive"))
      (node (ref "Q4") (pin "1") (pinfunction "S_1") (pintype "passive"))
      (node (ref "Q4") (pin "4") (pinfunction "S_4") (pintype "passive"))
      (node (ref "Q5") (pin "1") (pinfunction "S_1") (pintype "passive"))
      (node (ref "Q5") (pin "4") (pinfunction "S_4") (pintype "passive"))
      (node (ref "Q6") (pin "1") (pinfunction "S_1") (pintype "passive"))
      (node (ref "Q6") (pin "4") (pinfunction "S_4") (pintype "passive"))
      (node (ref "Q7") (pin "1") (pinfunction "S_1") (pintype "passive"))
      (node (ref "Q7") (pin "4") (pinfunction "S_4") (pintype "passive"))
      (node (ref "Q8") (pin "1") (pinfunction "S_1") (pintype "passive"))
      (node (ref "Q8") (pin "4") (pinfunction "S_4") (pintype "passive"))
      (node (ref "Q9") (pin "3") (pinfunction "D_3") (pintype "passive"))
      (node (ref "Q9") (pin "P2") (pinfunction "D_P2") (pintype "passive"))
      (node (ref "R11") (pin "2") (pinfunction "2_2") (pintype "passive"))
      (node (ref "R13") (pin "2") (pinfunction "2_2") (pintype "passive"))
      (node (ref "R5") (pin "2") (pinfunction "2_2") (pintype "passive"))
      (node (ref "R9") (pin "2") (pinfunction "2_2") (pintype "passive"))
      (node (ref "TP15") (pin "P$1") (pinfunction "P$1_P$1") (pintype "bidirectional"))
    )
    (net (code "40") (name "LED_COM_SENSE") (class "Default")
      (node (ref "C13") (pin "1") (pinfunction "1_1") (pintype "passive"))
      (node (ref "R5") (pin "1") (pinfunction "1_1") (pintype "passive"))
      (node (ref "U5") (pin "41") (pinfunction "GPIO29/ADC3_41") (pintype "bidirectional"))
    )
    (net (code "41") (name "LED_CURR_SENSE") (class "Default")
      (node (ref "C14") (pin "1") (pinfunction "1_1") (pintype "passive"))
      (node (ref "R4") (pin "1") (pinfunction "1_1") (pintype "passive"))
      (node (ref "U5") (pin "38") (pinfunction "GPIO26/ADC0_38") (pintype "bidirectional"))
    )
    (net (code "42") (name "LED_ENN") (class "Default")
      (node (ref "J1") (pin "4") (pinfunction "4_4") (pintype "passive"))
      (node (ref "U1") (pin "5") (pinfunction "G2B#_5") (pintype "input"))
      (node (ref "U2") (pin "5") (pinfunction "G2B#_5") (pintype "input"))
      (node (ref "U5") (pin "27") (pinfunction "GPIO16_27") (pintype "bidirectional"))
    )
    (net (code "43") (name "Net-(C10-Pad1)") (class "Default")
      (node (ref "C10") (pin "1") (pinfunction "1_1") (pintype "passive"))
      (node (ref "R9") (pin "1") (pinfunction "1_1") (pintype "passive"))
    )
    (net (code "44") (name "Net-(C11-Pad1)") (class "Default")
      (node (ref "C11") (pin "1") (pinfunction "1_1") (pintype "passive"))
      (node (ref "R11") (pin "1") (pinfunction "1_1") (pintype "passive"))
    )
    (net (code "45") (name "Net-(C12-Pad1)") (class "Default")
      (node (ref "C12") (pin "1") (pinfunction "1_1") (pintype "passive"))
      (node (ref "R13") (pin "1") (pinfunction "1_1") (pintype "passive"))
    )
    (net (code "46") (name "Net-(J4-SIGNAL)") (class "Default")
      (node (ref "J4") (pin "P$3") (pinfunction "SIGNAL_P$3") (pintype "bidirectional"))
      (node (ref "R10") (pin "2") (pinfunction "2_2") (pintype "passive"))
    )
    (net (code "47") (name "Net-(J7-Pad2)") (class "Default")
      (node (ref "J7") (pin "2") (pinfunction "2_2") (pintype "bidirectional"))
      (node (ref "R25") (pin "2") (pinfunction "2_2") (pintype "passive"))
    )
    (net (code "48") (name "Net-(J7-Pad3)") (class "Default")
      (node (ref "J7") (pin "3") (pinfunction "3_3") (pintype "bidirectional"))
      (node (ref "R24") (pin "2") (pinfunction "2_2") (pintype "passive"))
    )
    (net (code "49") (name "Net-(LED1-PadA)") (class "Default")
      (node (ref "LED1") (pin "A") (pinfunction "A_A") (pintype "passive"))
      (node (ref "R14") (pin "1") (pinfunction "1_1") (pintype "passive"))
    )
    (net (code "50") (name "Net-(LED2-PadA)") (class "Default")
      (node (ref "LED2") (pin "A") (pinfunction "A_A") (pintype "passive"))
      (node (ref "R15") (pin "1") (pinfunction "1_1") (pintype "passive"))
    )
    (net (code "51") (name "Net-(Q1A-G)") (class "Default")
      (node (ref "Q1") (pin "2") (pinfunction "G_2") (pintype "passive"))
      (node (ref "U2") (pin "11") (pinfunction "Y4_11") (pintype "output"))
    )
    (net (code "52") (name "Net-(Q1B-G)") (class "Default")
      (node (ref "Q1") (pin "5") (pinfunction "G_5") (pintype "passive"))
      (node (ref "U2") (pin "10") (pinfunction "Y5_10") (pintype "output"))
    )
    (net (code "53") (name "Net-(Q2A-G)") (class "Default")
      (node (ref "Q2") (pin "2") (pinfunction "G_2") (pintype "passive"))
      (node (ref "U2") (pin "15") (pinfunction "Y0_15") (pintype "output"))
    )
    (net (code "54") (name "Net-(Q2B-G)") (class "Default")
      (node (ref "Q2") (pin "5") (pinfunction "G_5") (pintype "passive"))
      (node (ref "U2") (pin "14") (pinfunction "Y1_14") (pintype "output"))
    )
    (net (code "55") (name "Net-(Q3A-G)") (class "Default")
      (node (ref "Q3") (pin "2") (pinfunction "G_2") (pintype "passive"))
      (node (ref "U1") (pin "11") (pinfunction "Y4_11") (pintype "output"))
    )
    (net (code "56") (name "Net-(Q3B-G)") (class "Default")
      (node (ref "Q3") (pin "5") (pinfunction "G_5") (pintype "passive"))
      (node (ref "TP14") (pin "P$1") (pinfunction "P$1_P$1") (pintype "bidirectional"))
      (node (ref "U1") (pin "10") (pinfunction "Y5_10") (pintype "output"))
    )
    (net (code "57") (name "Net-(Q4A-G)") (class "Default")
      (node (ref "Q4") (pin "2") (pinfunction "G_2") (pintype "passive"))
      (node (ref "U1") (pin "15") (pinfunction "Y0_15") (pintype "output"))
    )
    (net (code "58") (name "Net-(Q4B-G)") (class "Default")
      (node (ref "Q4") (pin "5") (pinfunction "G_5") (pintype "passive"))
      (node (ref "U1") (pin "14") (pinfunction "Y1_14") (pintype "output"))
    )
    (net (code "59") (name "Net-(Q5A-G)") (class "Default")
      (node (ref "Q5") (pin "2") (pinfunction "G_2") (pintype "passive"))
      (node (ref "U2") (pin "9") (pinfunction "Y6_9") (pintype "output"))
    )
    (net (code "60") (name "Net-(Q5B-G)") (class "Default")
      (node (ref "Q5") (pin "5") (pinfunction "G_5") (pintype "passive"))
      (node (ref "U2") (pin "7") (pinfunction "Y7_7") (pintype "output"))
    )
    (net (code "61") (name "Net-(Q6A-G)") (class "Default")
      (node (ref "Q6") (pin "2") (pinfunction "G_2") (pintype "passive"))
      (node (ref "U2") (pin "13") (pinfunction "Y2_13") (pintype "output"))
    )
    (net (code "62") (name "Net-(Q6B-G)") (class "Default")
      (node (ref "Q6") (pin "5") (pinfunction "G_5") (pintype "passive"))
      (node (ref "U2") (pin "12") (pinfunction "Y3_12") (pintype "output"))
    )
    (net (code "63") (name "Net-(Q7A-G)") (class "Default")
      (node (ref "Q7") (pin "2") (pinfunction "G_2") (pintype "passive"))
      (node (ref "U1") (pin "9") (pinfunction "Y6_9") (pintype "output"))
    )
    (net (code "64") (name "Net-(Q7B-G)") (class "Default")
      (node (ref "Q7") (pin "5") (pinfunction "G_5") (pintype "passive"))
      (node (ref "U1") (pin "7") (pinfunction "Y7_7") (pintype "output"))
    )
    (net (code "65") (name "Net-(Q8A-G)") (class "Default")
      (node (ref "Q8") (pin "2") (pinfunction "G_2") (pintype "passive"))
      (node (ref "U1") (pin "13") (pinfunction "Y2_13") (pintype "output"))
    )
    (net (code "66") (name "Net-(Q8B-G)") (class "Default")
      (node (ref "Q8") (pin "5") (pinfunction "G_5") (pintype "passive"))
      (node (ref "U1") (pin "12") (pinfunction "Y3_12") (pintype "output"))
    )
    (net (code "67") (name "Net-(Q9B-G)") (class "Default")
      (node (ref "Q9") (pin "5") (pinfunction "G_5") (pintype "passive"))
      (node (ref "R6") (pin "2") (pinfunction "2_2") (pintype "passive"))
    )
    (net (code "68") (name "Net-(Q9B-S)") (class "Default")
      (node (ref "Q9") (pin "4") (pinfunction "S_4") (pintype "passive"))
      (node (ref "R10") (pin "1") (pinfunction "1_1") (pintype "passive"))
      (node (ref "R4") (pin "2") (pinfunction "2_2") (pintype "passive"))
      (node (ref "R7") (pin "2") (pinfunction "2_2") (pintype "passive"))
      (node (ref "R8") (pin "2") (pinfunction "2_2") (pintype "passive"))
      (node (ref "TP4") (pin "P$1") (pinfunction "P$1_P$1") (pintype "bidirectional"))
    )
    (net (code "69") (name "Net-(Q10B-D-Pad3)") (class "Default")
      (node (ref "Q10") (pin "3") (pinfunction "D_3") (pintype "passive"))
      (node (ref "Q10") (pin "P2") (pinfunction "D_P2") (pintype "passive"))
      (node (ref "R12") (pin "1") (pinfunction "1_1") (pintype "passive"))
    )
    (net (code "70") (name "Net-(Q10B-G)") (class "Default")
      (node (ref "Q10") (pin "5") (pinfunction "G_5") (pintype "passive"))
      (node (ref "Q10") (pin "6") (pinfunction "D_6") (pintype "passive"))
      (node (ref "Q10") (pin "P1") (pinfunction "D_P1") (pintype "passive"))
      (node (ref "R32") (pin "1") (pinfunction "1_1") (pintype "passive"))
    )
    (net (code "71") (name "Net-(U3-VOUT)") (class "Default")
      (node (ref "R2") (pin "1") (pinfunction "1_1") (pintype "passive"))
      (node (ref "U3") (pin "10") (pinfunction "VOUT_10") (pintype "output"))
    )
    (net (code "72") (name "Net-(U3-VREF)") (class "Default")
      (node (ref "C4") (pin "1") (pinfunction "1_1") (pintype "passive"))
      (node (ref "U3") (pin "9") (pinfunction "VREF_9") (pintype "bidirectional"))
    )
    (net (code "73") (name "Net-(U4-+IN)") (class "Default")
      (node (ref "C6") (pin "1") (pinfunction "1_1") (pintype "passive"))
      (node (ref "R2") (pin "2") (pinfunction "2_2") (pintype "passive"))
      (node (ref "R3") (pin "2") (pinfunction "2_2") (pintype "passive"))
      (node (ref "TP3") (pin "P$1") (pinfunction "P$1_P$1") (pintype "bidirectional"))
      (node (ref "U4") (pin "3") (pinfunction "+IN_3") (pintype "input"))
    )
    (net (code "74") (name "Net-(U4--IN)") (class "Default")
      (node (ref "C9") (pin "2") (pinfunction "2_2") (pintype "passive"))
      (node (ref "R7") (pin "1") (pinfunction "1_1") (pintype "passive"))
      (node (ref "U4") (pin "4") (pinfunction "-IN_4") (pintype "input"))
    )
    (net (code "75") (name "Net-(U4-OUT)") (class "Default")
      (node (ref "C9") (pin "1") (pinfunction "1_1") (pintype "passive"))
      (node (ref "R6") (pin "1") (pinfunction "1_1") (pintype "passive"))
      (node (ref "U4") (pin "1") (pinfunction "OUT_1") (pintype "output"))
    )
    (net (code "76") (name "Net-(U5B-SWCLK)") (class "Default")
      (node (ref "R33") (pin "1") (pinfunction "1_1") (pintype "passive"))
      (node (ref "U5") (pin "24") (pinfunction "SWCLK_24") (pintype "input"))
    )
    (net (code "77") (name "Net-(U5B-SWDIO)") (class "Default")
      (node (ref "R34") (pin "1") (pinfunction "1_1") (pintype "passive"))
      (node (ref "U5") (pin "25") (pinfunction "SWDIO_25") (pintype "bidirectional"))
    )
    (net (code "78") (name "Net-(U5B-USB_DN)") (class "Default")
      (node (ref "R25") (pin "1") (pinfunction "1_1") (pintype "passive"))
      (node (ref "U5") (pin "46") (pinfunction "USB_DN_46") (pintype "bidirectional"))
    )
    (net (code "79") (name "Net-(U5B-USB_DP)") (class "Default")
      (node (ref "R24") (pin "1") (pinfunction "1_1") (pintype "passive"))
      (node (ref "U5") (pin "47") (pinfunction "USB_DP_47") (pintype "bidirectional"))
    )
    (net (code "80") (name "Net-(U5B-XIN)") (class "Default")
      (node (ref "C19") (pin "1") (pinfunction "1_1") (pintype "passive"))
      (node (ref "U5") (pin "20") (pinfunction "XIN_20") (pintype "bidirectional"))
      (node (ref "X1") (pin "3") (pinfunction "C2_3") (pintype "passive"))
    )
    (net (code "81") (name "Net-(U5B-XOUT)") (class "Default")
      (node (ref "R23") (pin "1") (pinfunction "1_1") (pintype "passive"))
      (node (ref "U5") (pin "21") (pinfunction "XOUT_21") (pintype "bidirectional"))
    )
    (net (code "82") (name "Net-(U5C-ADC_VDD)") (class "Default")
      (node (ref "C40") (pin "1") (pinfunction "1_1") (pintype "passive"))
      (node (ref "R31") (pin "2") (pinfunction "2_2") (pintype "passive"))
      (node (ref "U5") (pin "43") (pinfunction "ADC_VDD_43") (pintype "power_in"))
    )
    (net (code "83") (name "Net-(U9-ADJ{slash}SENSE)") (class "Default")
      (node (ref "R27") (pin "2") (pinfunction "2_2") (pintype "passive"))
      (node (ref "R29") (pin "1") (pinfunction "1_1") (pintype "passive"))
      (node (ref "U9") (pin "2") (pinfunction "ADJ/SENSE_2") (pintype "input"))
    )
    (net (code "84") (name "Net-(U10-ADJ{slash}SENSE)") (class "Default")
      (node (ref "R28") (pin "2") (pinfunction "2_2") (pintype "passive"))
      (node (ref "R30") (pin "1") (pinfunction "1_1") (pintype "passive"))
      (node (ref "U10") (pin "2") (pinfunction "ADJ/SENSE_2") (pintype "input"))
    )
    (net (code "85") (name "Net-(X1-C1)") (class "Default")
      (node (ref "C18") (pin "1") (pinfunction "1_1") (pintype "passive"))
      (node (ref "R23") (pin "2") (pinfunction "2_2") (pintype "passive"))
      (node (ref "X1") (pin "1") (pinfunction "C1_1") (pintype "passive"))
    )
    (net (code "86") (name "QSPI_SCLK") (class "Default")
      (node (ref "U5") (pin "52") (pinfunction "QSPI_SCLK_52") (pintype "output"))
      (node (ref "U6") (pin "6") (pinfunction "CLK_6") (pintype "input"))
    )
    (net (code "87") (name "QSPI_SD0") (class "Default")
      (node (ref "U5") (pin "53") (pinfunction "QSPI_SD0_53") (pintype "bidirectional"))
      (node (ref "U6") (pin "5") (pinfunction "DI/IO[0]_5") (pintype "bidirectional"))
    )
    (net (code "88") (name "QSPI_SD1") (class "Default")
      (node (ref "U5") (pin "55") (pinfunction "QSPI_SD1_55") (pintype "bidirectional"))
      (node (ref "U6") (pin "2") (pinfunction "DO/IO[1]_2") (pintype "bidirectional"))
    )
    (net (code "89") (name "QSPI_SD2") (class "Default")
      (node (ref "U5") (pin "54") (pinfunction "QSPI_SD2_54") (pintype "bidirectional"))
      (node (ref "U6") (pin "3") (pinfunction "#WP/IO[2]_3") (pintype "bidirectional"))
    )
    (net (code "90") (name "QSPI_SD3") (class "Default")
      (node (ref "U5") (pin "51") (pinfunction "QSPI_SD3_51") (pintype "bidirectional"))
      (node (ref "U6") (pin "7") (pinfunction "#HOLD/IO[3]_7") (pintype "bidirectional"))
    )
    (net (code "91") (name "QSPI_SS_N") (class "Default")
      (node (ref "R20") (pin "2") (pinfunction "2_2") (pintype "passive"))
      (node (ref "R22") (pin "1") (pinfunction "1_1") (pintype "passive"))
      (node (ref "U5") (pin "56") (pinfunction "QSPI_SS_N_56") (pintype "output"))
      (node (ref "U6") (pin "1") (pinfunction "/CS_1") (pintype "input"))
    )
    (net (code "92") (name "RUN") (class "Default")
      (node (ref "J5") (pin "B7") (pinfunction "13_B7") (pintype "passive"))
      (node (ref "R21") (pin "1") (pinfunction "1_1") (pintype "passive"))
      (node (ref "U5") (pin "26") (pinfunction "RUN_26") (pintype "input"))
    )
    (net (code "93") (name "SPARE0") (class "Default")
      (node (ref "TP5") (pin "P$1") (pinfunction "P$1_P$1") (pintype "bidirectional"))
      (node (ref "U5") (pin "30") (pinfunction "GPIO19_30") (pintype "bidirectional"))
    )
    (net (code "94") (name "SPARE1") (class "Default")
      (node (ref "TP6") (pin "P$1") (pinfunction "P$1_P$1") (pintype "bidirectional"))
      (node (ref "U5") (pin "31") (pinfunction "GPIO20_31") (pintype "bidirectional"))
    )
    (net (code "95") (name "SWCLK") (class "Default")
      (node (ref "J5") (pin "B6") (pinfunction "11_B6") (pintype "passive"))
      (node (ref "J6") (pin "1") (pinfunction "1_1") (pintype "passive"))
      (node (ref "R33") (pin "2") (pinfunction "2_2") (pintype "passive"))
    )
    (net (code "96") (name "SWDIO") (class "Default")
      (node (ref "J5") (pin "B5") (pinfunction "9_B5") (pintype "passive"))
      (node (ref "J6") (pin "3") (pinfunction "3_3") (pintype "passive"))
      (node (ref "R34") (pin "2") (pinfunction "2_2") (pintype "passive"))
    )
    (net (code "97") (name "V1P1") (class "Default")
      (node (ref "C33") (pin "1") (pinfunction "1_1") (pintype "passive"))
      (node (ref "C34") (pin "1") (pinfunction "1_1") (pintype "passive"))
      (node (ref "C35") (pin "1") (pinfunction "1_1") (pintype "passive"))
      (node (ref "TP12") (pin "P$1") (pinfunction "P$1_P$1") (pintype "bidirectional"))
      (node (ref "U5") (pin "23") (pinfunction "DVDD_23") (pintype "power_in"))
      (node (ref "U5") (pin "45") (pinfunction "VREG_VOUT_45") (pintype "power_in"))
      (node (ref "U5") (pin "50") (pinfunction "DVDD_50") (pintype "power_in"))
    )
    (net (code "98") (name "V3P3") (class "Default")
      (node (ref "C17") (pin "1") (pinfunction "1_1") (pintype "passive"))
      (node (ref "C26") (pin "1") (pinfunction "1_1") (pintype "passive"))
      (node (ref "C28") (pin "1") (pinfunction "1_1") (pintype "passive"))
      (node (ref "C36") (pin "1") (pinfunction "1_1") (pintype "passive"))
      (node (ref "C37") (pin "1") (pinfunction "1_1") (pintype "passive"))
      (node (ref "C38") (pin "1") (pinfunction "1_1") (pintype "passive"))
      (node (ref "C39") (pin "1") (pinfunction "1_1") (pintype "passive"))
      (node (ref "C41") (pin "1") (pinfunction "1_1") (pintype "passive"))
      (node (ref "C42") (pin "1") (pinfunction "1_1") (pintype "passive"))
      (node (ref "C43") (pin "1") (pinfunction "1_1") (pintype "passive"))
      (node (ref "C5") (pin "1") (pinfunction "1_1") (pintype "passive"))
      (node (ref "J5") (pin "B16") (pinfunction "31_B16") (pintype "passive"))
      (node (ref "Q10") (pin "2") (pinfunction "G_2") (pintype "passive"))
      (node (ref "R16") (pin "2") (pinfunction "2_2") (pintype "passive"))
      (node (ref "R21") (pin "2") (pinfunction "2_2") (pintype "passive"))
      (node (ref "R22") (pin "2") (pinfunction "2_2") (pintype "passive"))
      (node (ref "R31") (pin "1") (pinfunction "1_1") (pintype "passive"))
      (node (ref "TP8") (pin "P$1") (pinfunction "P$1_P$1") (pintype "bidirectional"))
      (node (ref "U3") (pin "2") (pinfunction "VLOGIC_2") (pintype "power_in"))
      (node (ref "U5") (pin "1") (pinfunction "IOVDD_1") (pintype "power_in"))
      (node (ref "U5") (pin "10") (pinfunction "IOVDD_10") (pintype "power_in"))
      (node (ref "U5") (pin "22") (pinfunction "IOVDD_22") (pintype "power_in"))
      (node (ref "U5") (pin "33") (pinfunction "IOVDD_33") (pintype "power_in"))
      (node (ref "U5") (pin "42") (pinfunction "IOVDD_42") (pintype "power_in"))
      (node (ref "U5") (pin "44") (pinfunction "VREG_VIN_44") (pintype "power_in"))
      (node (ref "U5") (pin "48") (pinfunction "USB_VDD_48") (pintype "power_in"))
      (node (ref "U5") (pin "49") (pinfunction "IOVDD_49") (pintype "power_in"))
      (node (ref "U6") (pin "8") (pinfunction "VCC_8") (pintype "power_in"))
      (node (ref "U8") (pin "1") (pinfunction "OUT_1") (pintype "power_in"))
    )
    (net (code "99") (name "V4P0") (class "Default")
      (node (ref "C1") (pin "1") (pinfunction "1_1") (pintype "passive"))
      (node (ref "C2") (pin "1") (pinfunction "1_1") (pintype "passive"))
      (node (ref "C29") (pin "1") (pinfunction "1_1") (pintype "passive"))
      (node (ref "C3") (pin "1") (pinfunction "1_1") (pintype "passive"))
      (node (ref "C31") (pin "1") (pinfunction "1_1") (pintype "passive"))
      (node (ref "C7") (pin "1") (pinfunction "1_1") (pintype "passive"))
      (node (ref "R29") (pin "2") (pinfunction "2_2") (pintype "passive"))
      (node (ref "R32") (pin "2") (pinfunction "2_2") (pintype "passive"))
      (node (ref "TP10") (pin "P$1") (pinfunction "P$1_P$1") (pintype "bidirectional"))
      (node (ref "U1") (pin "16") (pinfunction "VCC_16") (pintype "power_in"))
      (node (ref "U1") (pin "6") (pinfunction "G1_6") (pintype "input"))
      (node (ref "U2") (pin "16") (pinfunction "VCC_16") (pintype "power_in"))
      (node (ref "U3") (pin "1") (pinfunction "VDD_1") (pintype "power_in"))
      (node (ref "U4") (pin "5") (pinfunction "V+_5") (pintype "power_in"))
      (node (ref "U9") (pin "3") (pinfunction "VOUT_3") (pintype "power_in"))
    )
    (net (code "100") (name "VBUS") (class "Default")
      (node (ref "D10") (pin "1") (pinfunction "A1_1") (pintype "bidirectional"))
      (node (ref "D10") (pin "2") (pinfunction "A2_2") (pintype "bidirectional"))
      (node (ref "J7") (pin "1") (pinfunction "1_1") (pintype "bidirectional"))
    )
    (net (code "101") (name "VIN") (class "Default")
      (node (ref "D11") (pin "1") (pinfunction "A1_1") (pintype "bidirectional"))
      (node (ref "D11") (pin "2") (pinfunction "A2_2") (pintype "bidirectional"))
      (node (ref "F1") (pin "2") (pinfunction "2_2") (pintype "bidirectional"))
      (node (ref "J5") (pin "A1") (pinfunction "2_A1") (pintype "passive"))
      (node (ref "J5") (pin "A3") (pinfunction "6_A3") (pintype "passive"))
      (node (ref "J5") (pin "B1") (pinfunction "1_B1") (pintype "passive"))
      (node (ref "J5") (pin "B3") (pinfunction "5_B3") (pintype "passive"))
    )
    (net (code "102") (name "VIN_F") (class "Default")
      (node (ref "C20") (pin "P") (pinfunction "P_P") (pintype "passive"))
      (node (ref "C21") (pin "1") (pinfunction "1_1") (pintype "passive"))
      (node (ref "C23") (pin "1") (pinfunction "1_1") (pintype "passive"))
      (node (ref "C44") (pin "1") (pinfunction "1_1") (pintype "passive"))
      (node (ref "C45") (pin "1") (pinfunction "1_1") (pintype "passive"))
      (node (ref "F1") (pin "1") (pinfunction "1_1") (pintype "bidirectional"))
      (node (ref "R18") (pin "2") (pinfunction "2_2") (pintype "passive"))
      (node (ref "U10") (pin "4") (pinfunction "VIN_4") (pintype "power_in"))
      (node (ref "U9") (pin "4") (pinfunction "VIN_4") (pintype "power_in"))
      (node (ref "U9") (pin "6") (pinfunction "EN_6") (pintype "input"))
    )
    (net (code "103") (name "VIN_MCU") (class "Default")
      (node (ref "C22") (pin "1") (pinfunction "1_1") (pintype "passive"))
      (node (ref "C25") (pin "1") (pinfunction "1_1") (pintype "passive"))
      (node (ref "D10") (pin "3") (pinfunction "C_3") (pintype "bidirectional"))
      (node (ref "D11") (pin "3") (pinfunction "C_3") (pintype "bidirectional"))
      (node (ref "TP7") (pin "P$1") (pinfunction "P$1_P$1") (pintype "bidirectional"))
      (node (ref "U8") (pin "5") (pinfunction "/SHDN_5") (pintype "input"))
      (node (ref "U8") (pin "8") (pinfunction "IN_8") (pintype "power_in"))
    )
    (net (code "104") (name "VIN_SENSE") (class "Default")
      (node (ref "C16") (pin "1") (pinfunction "1_1") (pintype "passive"))
      (node (ref "R18") (pin "1") (pinfunction "1_1") (pintype "passive"))
      (node (ref "R19") (pin "2") (pinfunction "2_2") (pintype "passive"))
      (node (ref "U5") (pin "39") (pinfunction "GPIO27/ADC1_39") (pintype "bidirectional"))
    )
    (net (code "105") (name "VLED") (class "Default")
      (node (ref "C30") (pin "1") (pinfunction "1_1") (pintype "passive"))
      (node (ref "C32") (pin "1") (pinfunction "1_1") (pintype "passive"))
      (node (ref "C46") (pin "1") (pinfunction "1_1") (pintype "passive"))
      (node (ref "R1") (pin "2") (pinfunction "2_2") (pintype "passive"))
      (node (ref "R12") (pin "2") (pinfunction "2_2") (pintype "passive"))
      (node (ref "R30") (pin "2") (pinfunction "2_2") (pintype "passive"))
      (node (ref "TP11") (pin "P$1") (pinfunction "P$1_P$1") (pintype "bidirectional"))
      (node (ref "U10") (pin "3") (pinfunction "VOUT_3") (pintype "power_in"))
    )
    (net (code "106") (name "VLED_EN") (class "Default")
      (node (ref "R26") (pin "2") (pinfunction "2_2") (pintype "passive"))
      (node (ref "U10") (pin "6") (pinfunction "EN_6") (pintype "input"))
      (node (ref "U5") (pin "13") (pinfunction "GPIO10_13") (pintype "bidirectional"))
    )
    (net (code "107") (name "VN1P2") (class "Default")
      (node (ref "C27") (pin "2") (pinfunction "2_2") (pintype "passive"))
      (node (ref "C8") (pin "1") (pinfunction "1_1") (pintype "passive"))
      (node (ref "TP9") (pin "P$1") (pinfunction "P$1_P$1") (pintype "bidirectional"))
      (node (ref "U4") (pin "2") (pinfunction "V-_2") (pintype "power_in"))
      (node (ref "U7") (pin "1") (pinfunction "OUT_1") (pintype "bidirectional"))
      (node (ref "U7") (pin "2") (pinfunction "NC/ADJ_2") (pintype "bidirectional"))
    )
    (net (code "108") (name "VN3P0") (class "Default")
      (node (ref "C24") (pin "2") (pinfunction "2_2") (pintype "passive"))
      (node (ref "J5") (pin "A19") (pinfunction "38_A19") (pintype "passive"))
      (node (ref "R17") (pin "1") (pinfunction "1_1") (pintype "passive"))
      (node (ref "U7") (pin "3") (pinfunction "EN_3") (pintype "bidirectional"))
      (node (ref "U7") (pin "6") (pinfunction "IN_6") (pintype "bidirectional"))
      (node (ref "U7") (pin "PAD") (pinfunction "IN_PAD") (pintype "bidirectional"))
    )
    (net (code "109") (name "VN3P0_SENSE") (class "Default")
      (node (ref "C15") (pin "1") (pinfunction "1_1") (pintype "passive"))
      (node (ref "D9") (pin "3") (pinfunction "C_3") (pintype "bidirectional"))
      (node (ref "R16") (pin "1") (pinfunction "1_1") (pintype "passive"))
      (node (ref "R17") (pin "2") (pinfunction "2_2") (pintype "passive"))
      (node (ref "U5") (pin "40") (pinfunction "GPIO28/ADC2_40") (pintype "bidirectional"))
    )
    (net (code "110") (name "unconnected-(D9-A1-Pad1)") (class "Default")
      (node (ref "D9") (pin "1") (pinfunction "A1_1") (pintype "bidirectional"))
    )
    (net (code "111") (name "unconnected-(J5-36-PadA18)") (class "Default")
      (node (ref "J5") (pin "A18") (pinfunction "36_A18") (pintype "passive"))
    )
    (net (code "112") (name "unconnected-(J5-39-PadB20)") (class "Default")
      (node (ref "J5") (pin "B20") (pinfunction "39_B20") (pintype "passive"))
    )
    (net (code "113") (name "unconnected-(J7-Pad4)") (class "Default")
      (node (ref "J7") (pin "4") (pinfunction "4_4") (pintype "bidirectional"))
    )
    (net (code "114") (name "unconnected-(U5A-GPIO09-Pad12)") (class "Default")
      (node (ref "U5") (pin "12") (pinfunction "GPIO09_12") (pintype "bidirectional"))
    )
    (net (code "115") (name "unconnected-(U5A-GPIO11-Pad14)") (class "Default")
      (node (ref "U5") (pin "14") (pinfunction "GPIO11_14") (pintype "bidirectional"))
    )
    (net (code "116") (name "unconnected-(U5A-GPIO25-Pad37)") (class "Default")
      (node (ref "U5") (pin "37") (pinfunction "GPIO25_37") (pintype "bidirectional"))
    )
    (net (code "117") (name "unconnected-(U8-PWRGD-Pad2)") (class "Default")
      (node (ref "U8") (pin "2") (pinfunction "PWRGD_2") (pintype "output"))
    )
  )
)
